# Line.net
KiCad netlist of a schematic drawn in EAGLE
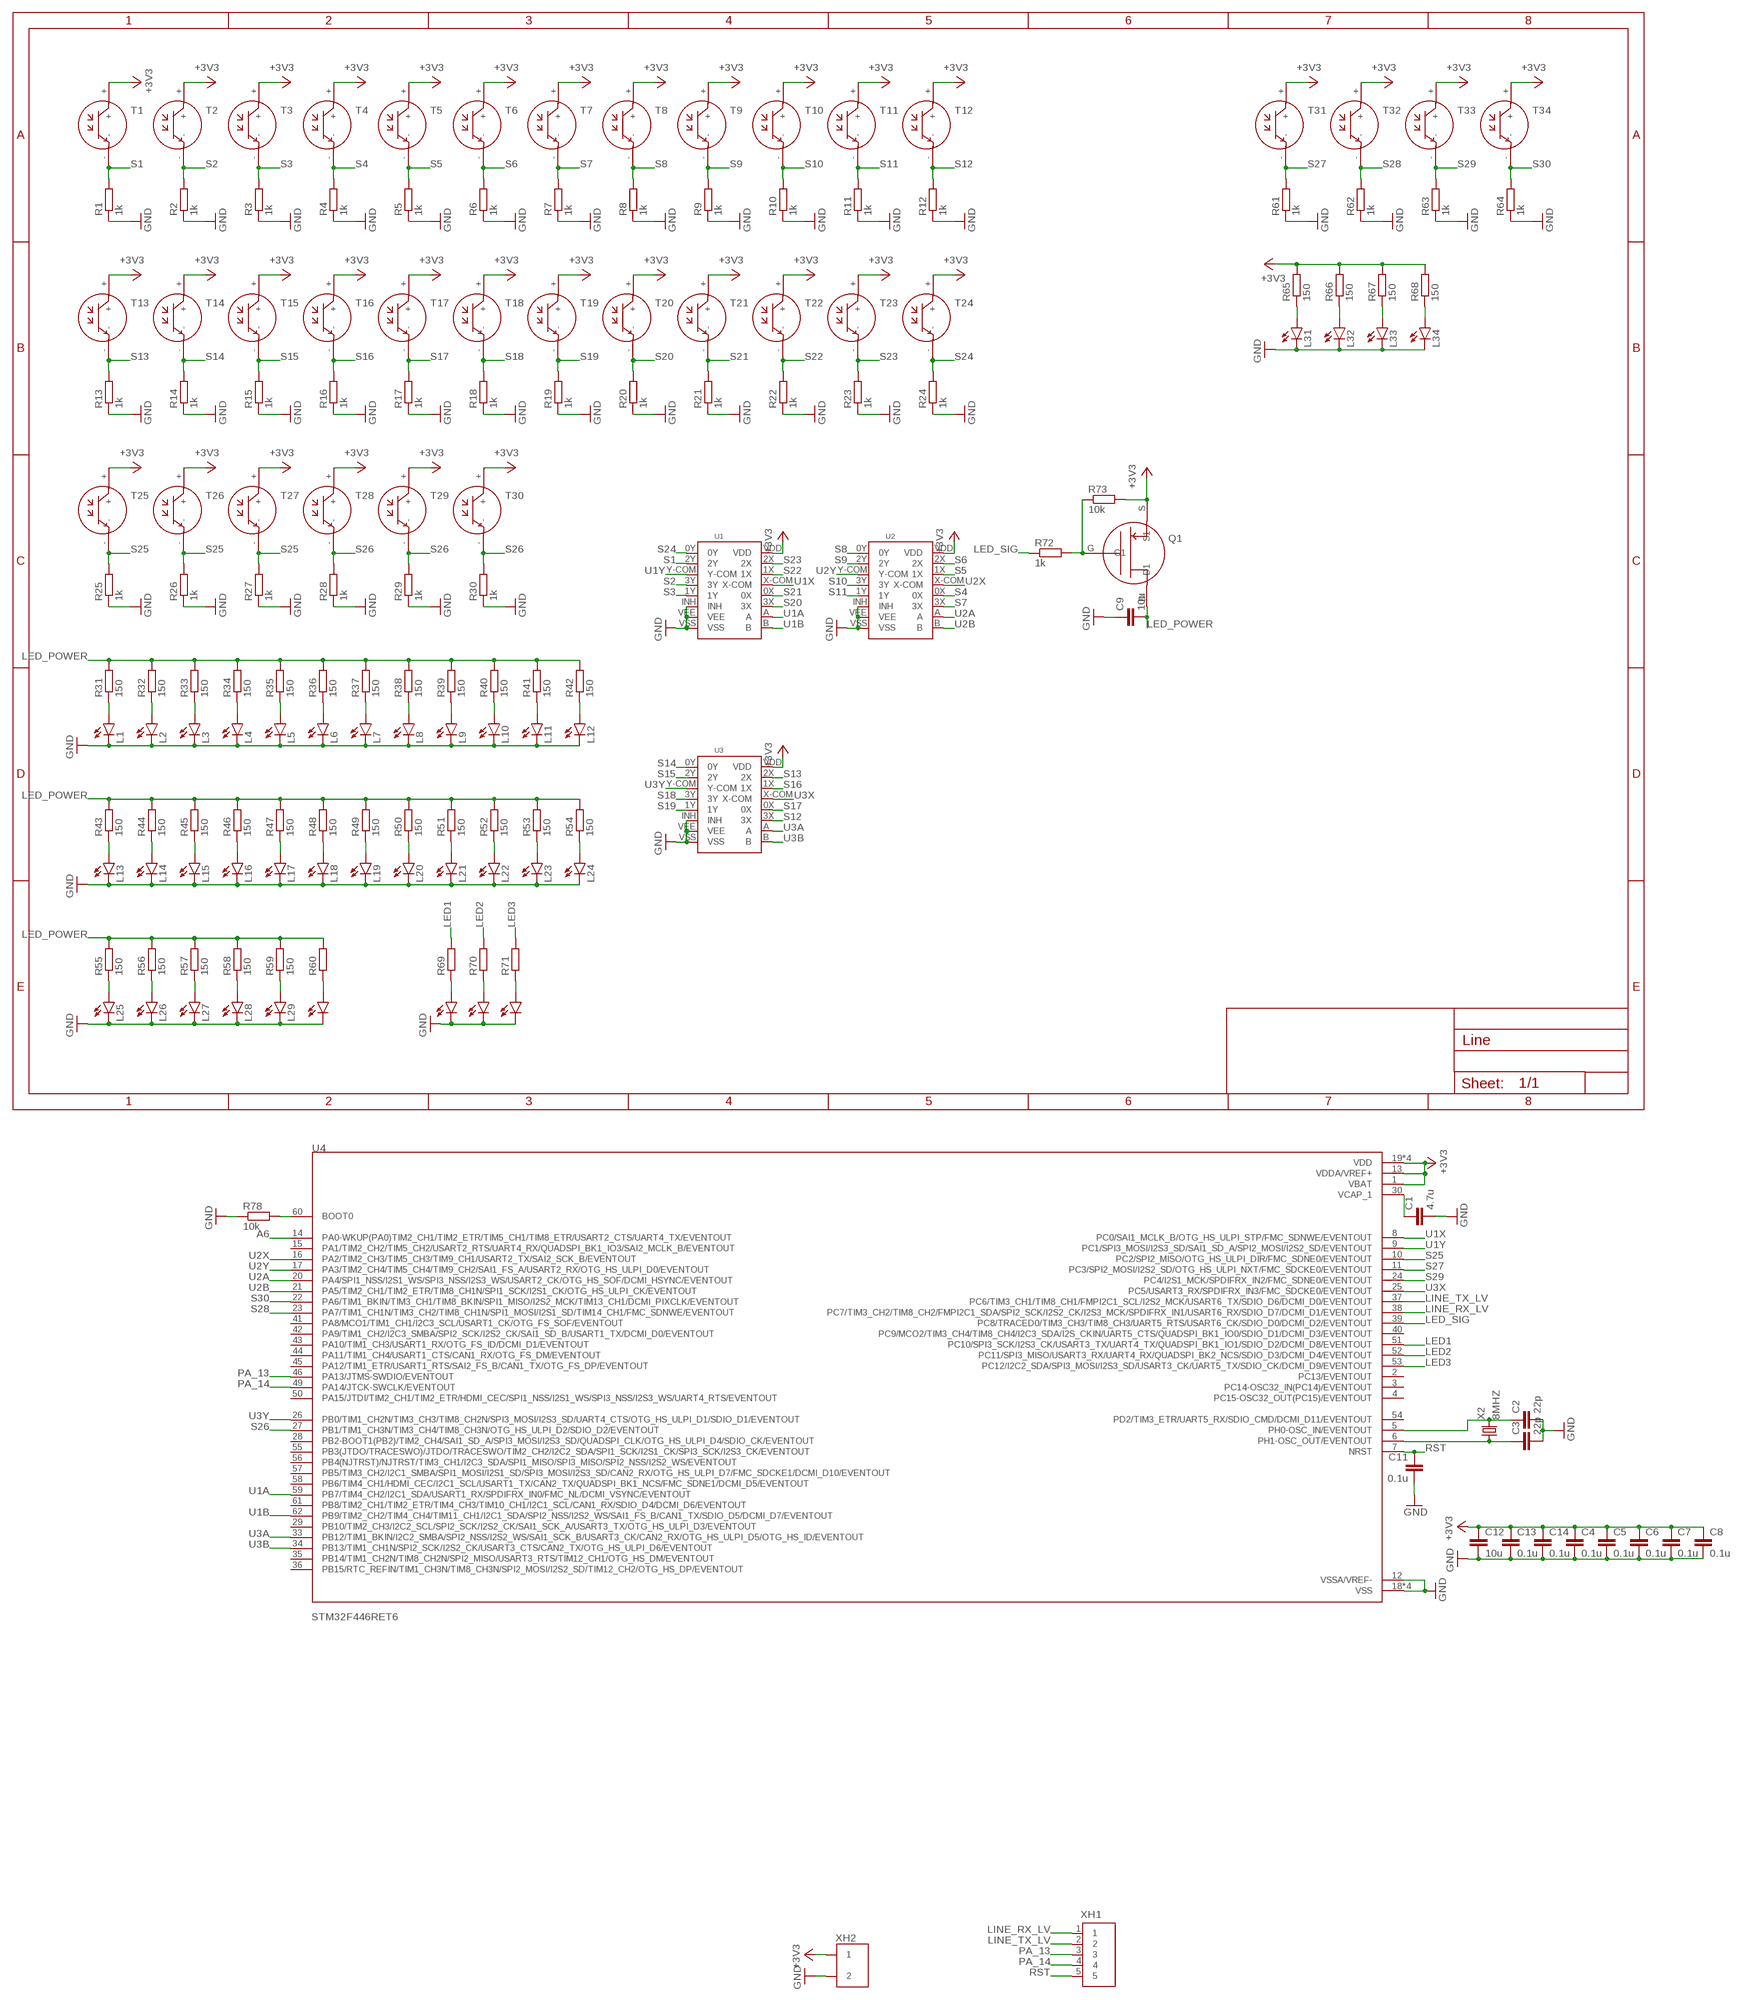
[diagram p0: schematic, sheet 1]

(export (version "E")
  (design (tool "Eeschema 10.0.6"))
  (components
    (comp (ref "C1")
      (value "4.7u")
      (footprint "eagle-import:C0603")
      (libsource (lib "eagle-import") (part "C-EUC0603"))
    )
    (comp (ref "C2")
      (value "22p")
      (footprint "eagle-import:C0603")
      (libsource (lib "eagle-import") (part "C-EUC0603"))
    )
    (comp (ref "C3")
      (value "22p")
      (footprint "eagle-import:C0603")
      (libsource (lib "eagle-import") (part "C-EUC0603"))
    )
    (comp (ref "C4")
      (value "0.1u")
      (footprint "eagle-import:C0603")
      (libsource (lib "eagle-import") (part "C-EUC0603"))
    )
    (comp (ref "C5")
      (value "0.1u")
      (footprint "eagle-import:C0603")
      (libsource (lib "eagle-import") (part "C-EUC0603"))
    )
    (comp (ref "C6")
      (value "0.1u")
      (footprint "eagle-import:C0603")
      (libsource (lib "eagle-import") (part "C-EUC0603"))
    )
    (comp (ref "C7")
      (value "0.1u")
      (footprint "eagle-import:C0603")
      (libsource (lib "eagle-import") (part "C-EUC0603"))
    )
    (comp (ref "C8")
      (value "0.1u")
      (footprint "eagle-import:C0603")
      (libsource (lib "eagle-import") (part "C-EUC0603"))
    )
    (comp (ref "C9")
      (value "10u")
      (footprint "eagle-import:C0805")
      (libsource (lib "eagle-import") (part "C-EUC0805"))
    )
    (comp (ref "C11")
      (value "0.1u")
      (footprint "eagle-import:C0603")
      (libsource (lib "eagle-import") (part "C-EUC0603"))
    )
    (comp (ref "C12")
      (value "10u")
      (footprint "eagle-import:C0805")
      (libsource (lib "eagle-import") (part "C-EUC0805"))
    )
    (comp (ref "C13")
      (value "0.1u")
      (footprint "eagle-import:C0603")
      (libsource (lib "eagle-import") (part "C-EUC0603"))
    )
    (comp (ref "C14")
      (value "0.1u")
      (footprint "eagle-import:C0603")
      (libsource (lib "eagle-import") (part "C-EUC0603"))
    )
    (comp (ref "L1")
      (value "SML-E12P8WT86")
      (footprint "eagle-import:LED_SML-LXFM0603SIC-TR")
      (libsource (lib "eagle-import") (part "SML-E12P8WT86"))
    )
    (comp (ref "L2")
      (value "SML-E12P8WT86")
      (footprint "eagle-import:LED_SML-LXFM0603SIC-TR")
      (libsource (lib "eagle-import") (part "SML-E12P8WT86"))
    )
    (comp (ref "L3")
      (value "SML-E12P8WT86")
      (footprint "eagle-import:LED_SML-LXFM0603SIC-TR")
      (libsource (lib "eagle-import") (part "SML-E12P8WT86"))
    )
    (comp (ref "L4")
      (value "SML-E12P8WT86")
      (footprint "eagle-import:LED_SML-LXFM0603SIC-TR")
      (libsource (lib "eagle-import") (part "SML-E12P8WT86"))
    )
    (comp (ref "L5")
      (value "SML-E12P8WT86")
      (footprint "eagle-import:LED_SML-LXFM0603SIC-TR")
      (libsource (lib "eagle-import") (part "SML-E12P8WT86"))
    )
    (comp (ref "L6")
      (value "SML-E12P8WT86")
      (footprint "eagle-import:LED_SML-LXFM0603SIC-TR")
      (libsource (lib "eagle-import") (part "SML-E12P8WT86"))
    )
    (comp (ref "L7")
      (value "SML-E12P8WT86")
      (footprint "eagle-import:LED_SML-LXFM0603SIC-TR")
      (libsource (lib "eagle-import") (part "SML-E12P8WT86"))
    )
    (comp (ref "L8")
      (value "SML-E12P8WT86")
      (footprint "eagle-import:LED_SML-LXFM0603SIC-TR")
      (libsource (lib "eagle-import") (part "SML-E12P8WT86"))
    )
    (comp (ref "L9")
      (value "SML-E12P8WT86")
      (footprint "eagle-import:LED_SML-LXFM0603SIC-TR")
      (libsource (lib "eagle-import") (part "SML-E12P8WT86"))
    )
    (comp (ref "L10")
      (value "SML-E12P8WT86")
      (footprint "eagle-import:LED_SML-LXFM0603SIC-TR")
      (libsource (lib "eagle-import") (part "SML-E12P8WT86"))
    )
    (comp (ref "L11")
      (value "SML-E12P8WT86")
      (footprint "eagle-import:LED_SML-LXFM0603SIC-TR")
      (libsource (lib "eagle-import") (part "SML-E12P8WT86"))
    )
    (comp (ref "L12")
      (value "SML-E12P8WT86")
      (footprint "eagle-import:LED_SML-LXFM0603SIC-TR")
      (libsource (lib "eagle-import") (part "SML-E12P8WT86"))
    )
    (comp (ref "L13")
      (value "SML-E12P8WT86")
      (footprint "eagle-import:LED_SML-LXFM0603SIC-TR")
      (libsource (lib "eagle-import") (part "SML-E12P8WT86"))
    )
    (comp (ref "L14")
      (value "SML-E12P8WT86")
      (footprint "eagle-import:LED_SML-LXFM0603SIC-TR")
      (libsource (lib "eagle-import") (part "SML-E12P8WT86"))
    )
    (comp (ref "L15")
      (value "SML-E12P8WT86")
      (footprint "eagle-import:LED_SML-LXFM0603SIC-TR")
      (libsource (lib "eagle-import") (part "SML-E12P8WT86"))
    )
    (comp (ref "L16")
      (value "SML-E12P8WT86")
      (footprint "eagle-import:LED_SML-LXFM0603SIC-TR")
      (libsource (lib "eagle-import") (part "SML-E12P8WT86"))
    )
    (comp (ref "L17")
      (value "SML-E12P8WT86")
      (footprint "eagle-import:LED_SML-LXFM0603SIC-TR")
      (libsource (lib "eagle-import") (part "SML-E12P8WT86"))
    )
    (comp (ref "L18")
      (value "SML-E12P8WT86")
      (footprint "eagle-import:LED_SML-LXFM0603SIC-TR")
      (libsource (lib "eagle-import") (part "SML-E12P8WT86"))
    )
    (comp (ref "L19")
      (value "SML-E12P8WT86")
      (footprint "eagle-import:LED_SML-LXFM0603SIC-TR")
      (libsource (lib "eagle-import") (part "SML-E12P8WT86"))
    )
    (comp (ref "L20")
      (value "SML-E12P8WT86")
      (footprint "eagle-import:LED_SML-LXFM0603SIC-TR")
      (libsource (lib "eagle-import") (part "SML-E12P8WT86"))
    )
    (comp (ref "L21")
      (value "SML-E12P8WT86")
      (footprint "eagle-import:LED_SML-LXFM0603SIC-TR")
      (libsource (lib "eagle-import") (part "SML-E12P8WT86"))
    )
    (comp (ref "L22")
      (value "SML-E12P8WT86")
      (footprint "eagle-import:LED_SML-LXFM0603SIC-TR")
      (libsource (lib "eagle-import") (part "SML-E12P8WT86"))
    )
    (comp (ref "L23")
      (value "SML-E12P8WT86")
      (footprint "eagle-import:LED_SML-LXFM0603SIC-TR")
      (libsource (lib "eagle-import") (part "SML-E12P8WT86"))
    )
    (comp (ref "L24")
      (value "SML-E12P8WT86")
      (footprint "eagle-import:LED_SML-LXFM0603SIC-TR")
      (libsource (lib "eagle-import") (part "SML-E12P8WT86"))
    )
    (comp (ref "L25")
      (value "SML-E12P8WT86")
      (footprint "eagle-import:LED_SML-LXFM0603SIC-TR")
      (libsource (lib "eagle-import") (part "SML-E12P8WT86"))
    )
    (comp (ref "L26")
      (value "SML-E12P8WT86")
      (footprint "eagle-import:LED_SML-LXFM0603SIC-TR")
      (libsource (lib "eagle-import") (part "SML-E12P8WT86"))
    )
    (comp (ref "L27")
      (value "SML-E12P8WT86")
      (footprint "eagle-import:LED_SML-LXFM0603SIC-TR")
      (libsource (lib "eagle-import") (part "SML-E12P8WT86"))
    )
    (comp (ref "L28")
      (value "SML-E12P8WT86")
      (footprint "eagle-import:LED_SML-LXFM0603SIC-TR")
      (libsource (lib "eagle-import") (part "SML-E12P8WT86"))
    )
    (comp (ref "L29")
      (value "SML-E12P8WT86")
      (footprint "eagle-import:LED_SML-LXFM0603SIC-TR")
      (libsource (lib "eagle-import") (part "SML-E12P8WT86"))
    )
    (comp (ref "L30")
      (value "SML-E12P8WT86")
      (footprint "eagle-import:LED_SML-LXFM0603SIC-TR")
      (libsource (lib "eagle-import") (part "SML-E12P8WT86"))
    )
    (comp (ref "L31")
      (value "SML-E12P8WT86")
      (footprint "eagle-import:LED_SML-LXFM0603SIC-TR")
      (libsource (lib "eagle-import") (part "SML-E12P8WT86"))
    )
    (comp (ref "L32")
      (value "SML-E12P8WT86")
      (footprint "eagle-import:LED_SML-LXFM0603SIC-TR")
      (libsource (lib "eagle-import") (part "SML-E12P8WT86"))
    )
    (comp (ref "L33")
      (value "SML-E12P8WT86")
      (footprint "eagle-import:LED_SML-LXFM0603SIC-TR")
      (libsource (lib "eagle-import") (part "SML-E12P8WT86"))
    )
    (comp (ref "L34")
      (value "SML-E12P8WT86")
      (footprint "eagle-import:LED_SML-LXFM0603SIC-TR")
      (libsource (lib "eagle-import") (part "SML-E12P8WT86"))
    )
    (comp (ref "L35")
      (value "SML-E12P8WT86")
      (footprint "eagle-import:LED_SML-LXFM0603SIC-TR")
      (libsource (lib "eagle-import") (part "SML-E12P8WT86"))
    )
    (comp (ref "L36")
      (value "SML-E12P8WT86")
      (footprint "eagle-import:LED_SML-LXFM0603SIC-TR")
      (libsource (lib "eagle-import") (part "SML-E12P8WT86"))
    )
    (comp (ref "L37")
      (value "SML-E12P8WT86")
      (footprint "eagle-import:LED_SML-LXFM0603SIC-TR")
      (libsource (lib "eagle-import") (part "SML-E12P8WT86"))
    )
    (comp (ref "Q1")
      (value "TJ60S04M3L")
      (footprint "eagle-import:DPACK")
      (libsource (lib "eagle-import") (part "TJ60S04M3L"))
    )
    (comp (ref "R1")
      (value "1k")
      (footprint "eagle-import:R0603")
      (libsource (lib "eagle-import") (part "R-EU_R0603"))
    )
    (comp (ref "R2")
      (value "1k")
      (footprint "eagle-import:R0603")
      (libsource (lib "eagle-import") (part "R-EU_R0603"))
    )
    (comp (ref "R3")
      (value "1k")
      (footprint "eagle-import:R0603")
      (libsource (lib "eagle-import") (part "R-EU_R0603"))
    )
    (comp (ref "R4")
      (value "1k")
      (footprint "eagle-import:R0603")
      (libsource (lib "eagle-import") (part "R-EU_R0603"))
    )
    (comp (ref "R5")
      (value "1k")
      (footprint "eagle-import:R0603")
      (libsource (lib "eagle-import") (part "R-EU_R0603"))
    )
    (comp (ref "R6")
      (value "1k")
      (footprint "eagle-import:R0603")
      (libsource (lib "eagle-import") (part "R-EU_R0603"))
    )
    (comp (ref "R7")
      (value "1k")
      (footprint "eagle-import:R0603")
      (libsource (lib "eagle-import") (part "R-EU_R0603"))
    )
    (comp (ref "R8")
      (value "1k")
      (footprint "eagle-import:R0603")
      (libsource (lib "eagle-import") (part "R-EU_R0603"))
    )
    (comp (ref "R9")
      (value "1k")
      (footprint "eagle-import:R0603")
      (libsource (lib "eagle-import") (part "R-EU_R0603"))
    )
    (comp (ref "R10")
      (value "1k")
      (footprint "eagle-import:R0603")
      (libsource (lib "eagle-import") (part "R-EU_R0603"))
    )
    (comp (ref "R11")
      (value "1k")
      (footprint "eagle-import:R0603")
      (libsource (lib "eagle-import") (part "R-EU_R0603"))
    )
    (comp (ref "R12")
      (value "1k")
      (footprint "eagle-import:R0603")
      (libsource (lib "eagle-import") (part "R-EU_R0603"))
    )
    (comp (ref "R13")
      (value "1k")
      (footprint "eagle-import:R0603")
      (libsource (lib "eagle-import") (part "R-EU_R0603"))
    )
    (comp (ref "R14")
      (value "1k")
      (footprint "eagle-import:R0603")
      (libsource (lib "eagle-import") (part "R-EU_R0603"))
    )
    (comp (ref "R15")
      (value "1k")
      (footprint "eagle-import:R0603")
      (libsource (lib "eagle-import") (part "R-EU_R0603"))
    )
    (comp (ref "R16")
      (value "1k")
      (footprint "eagle-import:R0603")
      (libsource (lib "eagle-import") (part "R-EU_R0603"))
    )
    (comp (ref "R17")
      (value "1k")
      (footprint "eagle-import:R0603")
      (libsource (lib "eagle-import") (part "R-EU_R0603"))
    )
    (comp (ref "R18")
      (value "1k")
      (footprint "eagle-import:R0603")
      (libsource (lib "eagle-import") (part "R-EU_R0603"))
    )
    (comp (ref "R19")
      (value "1k")
      (footprint "eagle-import:R0603")
      (libsource (lib "eagle-import") (part "R-EU_R0603"))
    )
    (comp (ref "R20")
      (value "1k")
      (footprint "eagle-import:R0603")
      (libsource (lib "eagle-import") (part "R-EU_R0603"))
    )
    (comp (ref "R21")
      (value "1k")
      (footprint "eagle-import:R0603")
      (libsource (lib "eagle-import") (part "R-EU_R0603"))
    )
    (comp (ref "R22")
      (value "1k")
      (footprint "eagle-import:R0603")
      (libsource (lib "eagle-import") (part "R-EU_R0603"))
    )
    (comp (ref "R23")
      (value "1k")
      (footprint "eagle-import:R0603")
      (libsource (lib "eagle-import") (part "R-EU_R0603"))
    )
    (comp (ref "R24")
      (value "1k")
      (footprint "eagle-import:R0603")
      (libsource (lib "eagle-import") (part "R-EU_R0603"))
    )
    (comp (ref "R25")
      (value "1k")
      (footprint "eagle-import:R0603")
      (libsource (lib "eagle-import") (part "R-EU_R0603"))
    )
    (comp (ref "R26")
      (value "1k")
      (footprint "eagle-import:R0603")
      (libsource (lib "eagle-import") (part "R-EU_R0603"))
    )
    (comp (ref "R27")
      (value "1k")
      (footprint "eagle-import:R0603")
      (libsource (lib "eagle-import") (part "R-EU_R0603"))
    )
    (comp (ref "R28")
      (value "1k")
      (footprint "eagle-import:R0603")
      (libsource (lib "eagle-import") (part "R-EU_R0603"))
    )
    (comp (ref "R29")
      (value "1k")
      (footprint "eagle-import:R0603")
      (libsource (lib "eagle-import") (part "R-EU_R0603"))
    )
    (comp (ref "R30")
      (value "1k")
      (footprint "eagle-import:R0603")
      (libsource (lib "eagle-import") (part "R-EU_R0603"))
    )
    (comp (ref "R31")
      (value "150")
      (footprint "eagle-import:R0603")
      (libsource (lib "eagle-import") (part "R-EU_R0603"))
    )
    (comp (ref "R32")
      (value "150")
      (footprint "eagle-import:R0603")
      (libsource (lib "eagle-import") (part "R-EU_R0603"))
    )
    (comp (ref "R33")
      (value "150")
      (footprint "eagle-import:R0603")
      (libsource (lib "eagle-import") (part "R-EU_R0603"))
    )
    (comp (ref "R34")
      (value "150")
      (footprint "eagle-import:R0603")
      (libsource (lib "eagle-import") (part "R-EU_R0603"))
    )
    (comp (ref "R35")
      (value "150")
      (footprint "eagle-import:R0603")
      (libsource (lib "eagle-import") (part "R-EU_R0603"))
    )
    (comp (ref "R36")
      (value "150")
      (footprint "eagle-import:R0603")
      (libsource (lib "eagle-import") (part "R-EU_R0603"))
    )
    (comp (ref "R37")
      (value "150")
      (footprint "eagle-import:R0603")
      (libsource (lib "eagle-import") (part "R-EU_R0603"))
    )
    (comp (ref "R38")
      (value "150")
      (footprint "eagle-import:R0603")
      (libsource (lib "eagle-import") (part "R-EU_R0603"))
    )
    (comp (ref "R39")
      (value "150")
      (footprint "eagle-import:R0603")
      (libsource (lib "eagle-import") (part "R-EU_R0603"))
    )
    (comp (ref "R40")
      (value "150")
      (footprint "eagle-import:R0603")
      (libsource (lib "eagle-import") (part "R-EU_R0603"))
    )
    (comp (ref "R41")
      (value "150")
      (footprint "eagle-import:R0603")
      (libsource (lib "eagle-import") (part "R-EU_R0603"))
    )
    (comp (ref "R42")
      (value "150")
      (footprint "eagle-import:R0603")
      (libsource (lib "eagle-import") (part "R-EU_R0603"))
    )
    (comp (ref "R43")
      (value "150")
      (footprint "eagle-import:R0603")
      (libsource (lib "eagle-import") (part "R-EU_R0603"))
    )
    (comp (ref "R44")
      (value "150")
      (footprint "eagle-import:R0603")
      (libsource (lib "eagle-import") (part "R-EU_R0603"))
    )
    (comp (ref "R45")
      (value "150")
      (footprint "eagle-import:R0603")
      (libsource (lib "eagle-import") (part "R-EU_R0603"))
    )
    (comp (ref "R46")
      (value "150")
      (footprint "eagle-import:R0603")
      (libsource (lib "eagle-import") (part "R-EU_R0603"))
    )
    (comp (ref "R47")
      (value "150")
      (footprint "eagle-import:R0603")
      (libsource (lib "eagle-import") (part "R-EU_R0603"))
    )
    (comp (ref "R48")
      (value "150")
      (footprint "eagle-import:R0603")
      (libsource (lib "eagle-import") (part "R-EU_R0603"))
    )
    (comp (ref "R49")
      (value "150")
      (footprint "eagle-import:R0603")
      (libsource (lib "eagle-import") (part "R-EU_R0603"))
    )
    (comp (ref "R50")
      (value "150")
      (footprint "eagle-import:R0603")
      (libsource (lib "eagle-import") (part "R-EU_R0603"))
    )
    (comp (ref "R51")
      (value "150")
      (footprint "eagle-import:R0603")
      (libsource (lib "eagle-import") (part "R-EU_R0603"))
    )
    (comp (ref "R52")
      (value "150")
      (footprint "eagle-import:R0603")
      (libsource (lib "eagle-import") (part "R-EU_R0603"))
    )
    (comp (ref "R53")
      (value "150")
      (footprint "eagle-import:R0603")
      (libsource (lib "eagle-import") (part "R-EU_R0603"))
    )
    (comp (ref "R54")
      (value "150")
      (footprint "eagle-import:R0603")
      (libsource (lib "eagle-import") (part "R-EU_R0603"))
    )
    (comp (ref "R55")
      (value "150")
      (footprint "eagle-import:R0603")
      (libsource (lib "eagle-import") (part "R-EU_R0603"))
    )
    (comp (ref "R56")
      (value "150")
      (footprint "eagle-import:R0603")
      (libsource (lib "eagle-import") (part "R-EU_R0603"))
    )
    (comp (ref "R57")
      (value "150")
      (footprint "eagle-import:R0603")
      (libsource (lib "eagle-import") (part "R-EU_R0603"))
    )
    (comp (ref "R58")
      (value "150")
      (footprint "eagle-import:R0603")
      (libsource (lib "eagle-import") (part "R-EU_R0603"))
    )
    (comp (ref "R59")
      (value "150")
      (footprint "eagle-import:R0603")
      (libsource (lib "eagle-import") (part "R-EU_R0603"))
    )
    (comp (ref "R60")
      (value "150")
      (footprint "eagle-import:R0603")
      (libsource (lib "eagle-import") (part "R-EU_R0603"))
    )
    (comp (ref "R61")
      (value "1k")
      (footprint "eagle-import:R0603")
      (libsource (lib "eagle-import") (part "R-EU_R0603"))
    )
    (comp (ref "R62")
      (value "1k")
      (footprint "eagle-import:R0603")
      (libsource (lib "eagle-import") (part "R-EU_R0603"))
    )
    (comp (ref "R63")
      (value "1k")
      (footprint "eagle-import:R0603")
      (libsource (lib "eagle-import") (part "R-EU_R0603"))
    )
    (comp (ref "R64")
      (value "1k")
      (footprint "eagle-import:R0603")
      (libsource (lib "eagle-import") (part "R-EU_R0603"))
    )
    (comp (ref "R65")
      (value "150")
      (footprint "eagle-import:R0603")
      (libsource (lib "eagle-import") (part "R-EU_R0603"))
    )
    (comp (ref "R66")
      (value "150")
      (footprint "eagle-import:R0603")
      (libsource (lib "eagle-import") (part "R-EU_R0603"))
    )
    (comp (ref "R67")
      (value "150")
      (footprint "eagle-import:R0603")
      (libsource (lib "eagle-import") (part "R-EU_R0603"))
    )
    (comp (ref "R68")
      (value "150")
      (footprint "eagle-import:R0603")
      (libsource (lib "eagle-import") (part "R-EU_R0603"))
    )
    (comp (ref "R69")
      (value "150")
      (footprint "eagle-import:R0603")
      (libsource (lib "eagle-import") (part "R-EU_R0603"))
    )
    (comp (ref "R70")
      (value "150")
      (footprint "eagle-import:R0603")
      (libsource (lib "eagle-import") (part "R-EU_R0603"))
    )
    (comp (ref "R71")
      (value "150")
      (footprint "eagle-import:R0603")
      (libsource (lib "eagle-import") (part "R-EU_R0603"))
    )
    (comp (ref "R72")
      (value "1k")
      (footprint "eagle-import:R0603")
      (libsource (lib "eagle-import") (part "R-EU_R0603"))
    )
    (comp (ref "R73")
      (value "10k")
      (footprint "eagle-import:R0603")
      (libsource (lib "eagle-import") (part "R-EU_R0603"))
    )
    (comp (ref "R78")
      (value "10k")
      (footprint "eagle-import:R0603")
      (libsource (lib "eagle-import") (part "R-EU_R0603"))
    )
    (comp (ref "T1")
      (value "NJL7302L-F3")
      (footprint "eagle-import:NJL7302L-F3")
      (libsource (lib "eagle-import") (part "NJL7302L-F3"))
    )
    (comp (ref "T2")
      (value "NJL7302L-F3")
      (footprint "eagle-import:NJL7302L-F3")
      (libsource (lib "eagle-import") (part "NJL7302L-F3"))
    )
    (comp (ref "T3")
      (value "NJL7302L-F3")
      (footprint "eagle-import:NJL7302L-F3")
      (libsource (lib "eagle-import") (part "NJL7302L-F3"))
    )
    (comp (ref "T4")
      (value "NJL7302L-F3")
      (footprint "eagle-import:NJL7302L-F3")
      (libsource (lib "eagle-import") (part "NJL7302L-F3"))
    )
    (comp (ref "T5")
      (value "NJL7302L-F3")
      (footprint "eagle-import:NJL7302L-F3")
      (libsource (lib "eagle-import") (part "NJL7302L-F3"))
    )
    (comp (ref "T6")
      (value "NJL7302L-F3")
      (footprint "eagle-import:NJL7302L-F3")
      (libsource (lib "eagle-import") (part "NJL7302L-F3"))
    )
    (comp (ref "T7")
      (value "NJL7302L-F3")
      (footprint "eagle-import:NJL7302L-F3")
      (libsource (lib "eagle-import") (part "NJL7302L-F3"))
    )
    (comp (ref "T8")
      (value "NJL7302L-F3")
      (footprint "eagle-import:NJL7302L-F3")
      (libsource (lib "eagle-import") (part "NJL7302L-F3"))
    )
    (comp (ref "T9")
      (value "NJL7302L-F3")
      (footprint "eagle-import:NJL7302L-F3")
      (libsource (lib "eagle-import") (part "NJL7302L-F3"))
    )
    (comp (ref "T10")
      (value "NJL7302L-F3")
      (footprint "eagle-import:NJL7302L-F3")
      (libsource (lib "eagle-import") (part "NJL7302L-F3"))
    )
    (comp (ref "T11")
      (value "NJL7302L-F3")
      (footprint "eagle-import:NJL7302L-F3")
      (libsource (lib "eagle-import") (part "NJL7302L-F3"))
    )
    (comp (ref "T12")
      (value "NJL7302L-F3")
      (footprint "eagle-import:NJL7302L-F3")
      (libsource (lib "eagle-import") (part "NJL7302L-F3"))
    )
    (comp (ref "T13")
      (value "NJL7302L-F3")
      (footprint "eagle-import:NJL7302L-F3")
      (libsource (lib "eagle-import") (part "NJL7302L-F3"))
    )
    (comp (ref "T14")
      (value "NJL7302L-F3")
      (footprint "eagle-import:NJL7302L-F3")
      (libsource (lib "eagle-import") (part "NJL7302L-F3"))
    )
    (comp (ref "T15")
      (value "NJL7302L-F3")
      (footprint "eagle-import:NJL7302L-F3")
      (libsource (lib "eagle-import") (part "NJL7302L-F3"))
    )
    (comp (ref "T16")
      (value "NJL7302L-F3")
      (footprint "eagle-import:NJL7302L-F3")
      (libsource (lib "eagle-import") (part "NJL7302L-F3"))
    )
    (comp (ref "T17")
      (value "NJL7302L-F3")
      (footprint "eagle-import:NJL7302L-F3")
      (libsource (lib "eagle-import") (part "NJL7302L-F3"))
    )
    (comp (ref "T18")
      (value "NJL7302L-F3")
      (footprint "eagle-import:NJL7302L-F3")
      (libsource (lib "eagle-import") (part "NJL7302L-F3"))
    )
    (comp (ref "T19")
      (value "NJL7302L-F3")
      (footprint "eagle-import:NJL7302L-F3")
      (libsource (lib "eagle-import") (part "NJL7302L-F3"))
    )
    (comp (ref "T20")
      (value "NJL7302L-F3")
      (footprint "eagle-import:NJL7302L-F3")
      (libsource (lib "eagle-import") (part "NJL7302L-F3"))
    )
    (comp (ref "T21")
      (value "NJL7302L-F3")
      (footprint "eagle-import:NJL7302L-F3")
      (libsource (lib "eagle-import") (part "NJL7302L-F3"))
    )
    (comp (ref "T22")
      (value "NJL7302L-F3")
      (footprint "eagle-import:NJL7302L-F3")
      (libsource (lib "eagle-import") (part "NJL7302L-F3"))
    )
    (comp (ref "T23")
      (value "NJL7302L-F3")
      (footprint "eagle-import:NJL7302L-F3")
      (libsource (lib "eagle-import") (part "NJL7302L-F3"))
    )
    (comp (ref "T24")
      (value "NJL7302L-F3")
      (footprint "eagle-import:NJL7302L-F3")
      (libsource (lib "eagle-import") (part "NJL7302L-F3"))
    )
    (comp (ref "T25")
      (value "NJL7302L-F3")
      (footprint "eagle-import:NJL7302L-F3")
      (libsource (lib "eagle-import") (part "NJL7302L-F3"))
    )
    (comp (ref "T26")
      (value "NJL7302L-F3")
      (footprint "eagle-import:NJL7302L-F3")
      (libsource (lib "eagle-import") (part "NJL7302L-F3"))
    )
    (comp (ref "T27")
      (value "NJL7302L-F3")
      (footprint "eagle-import:NJL7302L-F3")
      (libsource (lib "eagle-import") (part "NJL7302L-F3"))
    )
    (comp (ref "T28")
      (value "NJL7302L-F3")
      (footprint "eagle-import:NJL7302L-F3")
      (libsource (lib "eagle-import") (part "NJL7302L-F3"))
    )
    (comp (ref "T29")
      (value "NJL7302L-F3")
      (footprint "eagle-import:NJL7302L-F3")
      (libsource (lib "eagle-import") (part "NJL7302L-F3"))
    )
    (comp (ref "T30")
      (value "NJL7302L-F3")
      (footprint "eagle-import:NJL7302L-F3")
      (libsource (lib "eagle-import") (part "NJL7302L-F3"))
    )
    (comp (ref "T31")
      (value "NJL7302L-F3")
      (footprint "eagle-import:NJL7302L-F3")
      (libsource (lib "eagle-import") (part "NJL7302L-F3"))
    )
    (comp (ref "T32")
      (value "NJL7302L-F3")
      (footprint "eagle-import:NJL7302L-F3")
      (libsource (lib "eagle-import") (part "NJL7302L-F3"))
    )
    (comp (ref "T33")
      (value "NJL7302L-F3")
      (footprint "eagle-import:NJL7302L-F3")
      (libsource (lib "eagle-import") (part "NJL7302L-F3"))
    )
    (comp (ref "T34")
      (value "NJL7302L-F3")
      (footprint "eagle-import:NJL7302L-F3")
      (libsource (lib "eagle-import") (part "NJL7302L-F3"))
    )
    (comp (ref "U1")
      (value "TC4051BP")
      (footprint "eagle-import:TC4051BP")
      (libsource (lib "eagle-import") (part "TC4051BP"))
    )
    (comp (ref "U2")
      (value "TC4051BP")
      (footprint "eagle-import:TC4051BP")
      (libsource (lib "eagle-import") (part "TC4051BP"))
    )
    (comp (ref "U3")
      (value "TC4051BP")
      (footprint "eagle-import:TC4051BP")
      (libsource (lib "eagle-import") (part "TC4051BP"))
    )
    (comp (ref "U4")
      (value "STM32F446RET6")
      (footprint "eagle-import:QFP50P1200X1200X160-64N")
      (fields (field (name "MF") "STMicroelectronics"))
      (libsource (lib "eagle-import") (part "STM32F446RET6"))
    )
    (comp (ref "X2")
      (value "8MHZ")
      (footprint "eagle-import:16MHZ")
      (libsource (lib "eagle-import") (part "16MHZ"))
    )
    (comp (ref "XH1") (value "5B") (footprint "eagle-import:5B") (libsource (lib "eagle-import") (part "5B")))
    (comp (ref "XH2") (value "2B") (footprint "eagle-import:2B") (libsource (lib "eagle-import") (part "2B")))
  )
  (nets
    (net (code "1") (name "+3V3") (class "Default")
      (node (ref "C12") (pin "1") (pinfunction "1_1") (pintype "passive"))
      (node (ref "C13") (pin "1") (pinfunction "1_1") (pintype "passive"))
      (node (ref "C14") (pin "1") (pinfunction "1_1") (pintype "passive"))
      (node (ref "C4") (pin "1") (pinfunction "1_1") (pintype "passive"))
      (node (ref "C5") (pin "1") (pinfunction "1_1") (pintype "passive"))
      (node (ref "C6") (pin "1") (pinfunction "1_1") (pintype "passive"))
      (node (ref "C7") (pin "1") (pinfunction "1_1") (pintype "passive"))
      (node (ref "C8") (pin "1") (pinfunction "1_1") (pintype "passive"))
      (node (ref "Q1") (pin "S") (pinfunction "S1_S") (pintype "bidirectional"))
      (node (ref "R65") (pin "2") (pinfunction "2_2") (pintype "passive"))
      (node (ref "R66") (pin "2") (pinfunction "2_2") (pintype "passive"))
      (node (ref "R67") (pin "2") (pinfunction "2_2") (pintype "passive"))
      (node (ref "R68") (pin "2") (pinfunction "2_2") (pintype "passive"))
      (node (ref "R73") (pin "2") (pinfunction "2_2") (pintype "passive"))
      (node (ref "T1") (pin "+") (pinfunction "+_+") (pintype "bidirectional"))
      (node (ref "T10") (pin "+") (pinfunction "+_+") (pintype "bidirectional"))
      (node (ref "T11") (pin "+") (pinfunction "+_+") (pintype "bidirectional"))
      (node (ref "T12") (pin "+") (pinfunction "+_+") (pintype "bidirectional"))
      (node (ref "T13") (pin "+") (pinfunction "+_+") (pintype "bidirectional"))
      (node (ref "T14") (pin "+") (pinfunction "+_+") (pintype "bidirectional"))
      (node (ref "T15") (pin "+") (pinfunction "+_+") (pintype "bidirectional"))
      (node (ref "T16") (pin "+") (pinfunction "+_+") (pintype "bidirectional"))
      (node (ref "T17") (pin "+") (pinfunction "+_+") (pintype "bidirectional"))
      (node (ref "T18") (pin "+") (pinfunction "+_+") (pintype "bidirectional"))
      (node (ref "T19") (pin "+") (pinfunction "+_+") (pintype "bidirectional"))
      (node (ref "T2") (pin "+") (pinfunction "+_+") (pintype "bidirectional"))
      (node (ref "T20") (pin "+") (pinfunction "+_+") (pintype "bidirectional"))
      (node (ref "T21") (pin "+") (pinfunction "+_+") (pintype "bidirectional"))
      (node (ref "T22") (pin "+") (pinfunction "+_+") (pintype "bidirectional"))
      (node (ref "T23") (pin "+") (pinfunction "+_+") (pintype "bidirectional"))
      (node (ref "T24") (pin "+") (pinfunction "+_+") (pintype "bidirectional"))
      (node (ref "T25") (pin "+") (pinfunction "+_+") (pintype "bidirectional"))
      (node (ref "T26") (pin "+") (pinfunction "+_+") (pintype "bidirectional"))
      (node (ref "T27") (pin "+") (pinfunction "+_+") (pintype "bidirectional"))
      (node (ref "T28") (pin "+") (pinfunction "+_+") (pintype "bidirectional"))
      (node (ref "T29") (pin "+") (pinfunction "+_+") (pintype "bidirectional"))
      (node (ref "T3") (pin "+") (pinfunction "+_+") (pintype "bidirectional"))
      (node (ref "T30") (pin "+") (pinfunction "+_+") (pintype "bidirectional"))
      (node (ref "T31") (pin "+") (pinfunction "+_+") (pintype "bidirectional"))
      (node (ref "T32") (pin "+") (pinfunction "+_+") (pintype "bidirectional"))
      (node (ref "T33") (pin "+") (pinfunction "+_+") (pintype "bidirectional"))
      (node (ref "T34") (pin "+") (pinfunction "+_+") (pintype "bidirectional"))
      (node (ref "T4") (pin "+") (pinfunction "+_+") (pintype "bidirectional"))
      (node (ref "T5") (pin "+") (pinfunction "+_+") (pintype "bidirectional"))
      (node (ref "T6") (pin "+") (pinfunction "+_+") (pintype "bidirectional"))
      (node (ref "T7") (pin "+") (pinfunction "+_+") (pintype "bidirectional"))
      (node (ref "T8") (pin "+") (pinfunction "+_+") (pintype "bidirectional"))
      (node (ref "T9") (pin "+") (pinfunction "+_+") (pintype "bidirectional"))
      (node (ref "U1") (pin "VDD") (pinfunction "VDD_VDD") (pintype "bidirectional"))
      (node (ref "U2") (pin "VDD") (pinfunction "VDD_VDD") (pintype "bidirectional"))
      (node (ref "U3") (pin "VDD") (pinfunction "VDD_VDD") (pintype "bidirectional"))
      (node (ref "U4") (pin "1") (pinfunction "VBAT_1") (pintype "power_in"))
      (node (ref "U4") (pin "13") (pinfunction "VDDA/VREF+_13") (pintype "power_in"))
      (node (ref "U4") (pin "19") (pinfunction "VDD_19") (pintype "power_in"))
      (node (ref "U4") (pin "32") (pinfunction "VDD_32") (pintype "power_in"))
      (node (ref "U4") (pin "48") (pinfunction "VDD_48") (pintype "power_in"))
      (node (ref "U4") (pin "64") (pinfunction "VDD_64") (pintype "power_in"))
      (node (ref "XH2") (pin "P$1") (pinfunction "1_P$1") (pintype "bidirectional"))
    )
    (net (code "2") (name "/A6") (class "Default")
      (node (ref "U4") (pin "14") (pinfunction "PA0-WKUP(PA0)TIM2_CH1/TIM2_ETR/TIM5_CH1/TIM8_ETR/USART2_CTS/UART4_TX/EVENTOUT_14") (pintype "bidirectional"))
    )
    (net (code "3") (name "/LED1") (class "Default")
      (node (ref "R69") (pin "2") (pinfunction "2_2") (pintype "passive"))
      (node (ref "U4") (pin "51") (pinfunction "PC10/SPI3_SCK/I2S3_CK/USART3_TX/UART4_TX/QUADSPI_BK1_IO1/SDIO_D2/DCMI_D8/EVENTOUT_51") (pintype "bidirectional"))
    )
    (net (code "4") (name "/LED2") (class "Default")
      (node (ref "R70") (pin "2") (pinfunction "2_2") (pintype "passive"))
      (node (ref "U4") (pin "52") (pinfunction "PC11/SPI3_MISO/USART3_RX/UART4_RX/QUADSPI_BK2_NCS/SDIO_D3/DCMI_D4/EVENTOUT_52") (pintype "bidirectional"))
    )
    (net (code "5") (name "/LED3") (class "Default")
      (node (ref "R71") (pin "2") (pinfunction "2_2") (pintype "passive"))
      (node (ref "U4") (pin "53") (pinfunction "PC12/I2C2_SDA/SPI3_MOSI/I2S3_SD/USART3_CK/UART5_TX/SDIO_CK/DCMI_D9/EVENTOUT_53") (pintype "bidirectional"))
    )
    (net (code "6") (name "/LED_POWER") (class "Default")
      (node (ref "C9") (pin "2") (pinfunction "2_2") (pintype "passive"))
      (node (ref "Q1") (pin "D") (pinfunction "D1_D") (pintype "bidirectional"))
      (node (ref "R31") (pin "2") (pinfunction "2_2") (pintype "passive"))
      (node (ref "R32") (pin "2") (pinfunction "2_2") (pintype "passive"))
      (node (ref "R33") (pin "2") (pinfunction "2_2") (pintype "passive"))
      (node (ref "R34") (pin "2") (pinfunction "2_2") (pintype "passive"))
      (node (ref "R35") (pin "2") (pinfunction "2_2") (pintype "passive"))
      (node (ref "R36") (pin "2") (pinfunction "2_2") (pintype "passive"))
      (node (ref "R37") (pin "2") (pinfunction "2_2") (pintype "passive"))
      (node (ref "R38") (pin "2") (pinfunction "2_2") (pintype "passive"))
      (node (ref "R39") (pin "2") (pinfunction "2_2") (pintype "passive"))
      (node (ref "R40") (pin "2") (pinfunction "2_2") (pintype "passive"))
      (node (ref "R41") (pin "2") (pinfunction "2_2") (pintype "passive"))
      (node (ref "R42") (pin "2") (pinfunction "2_2") (pintype "passive"))
      (node (ref "R43") (pin "2") (pinfunction "2_2") (pintype "passive"))
      (node (ref "R44") (pin "2") (pinfunction "2_2") (pintype "passive"))
      (node (ref "R45") (pin "2") (pinfunction "2_2") (pintype "passive"))
      (node (ref "R46") (pin "2") (pinfunction "2_2") (pintype "passive"))
      (node (ref "R47") (pin "2") (pinfunction "2_2") (pintype "passive"))
      (node (ref "R48") (pin "2") (pinfunction "2_2") (pintype "passive"))
      (node (ref "R49") (pin "2") (pinfunction "2_2") (pintype "passive"))
      (node (ref "R50") (pin "2") (pinfunction "2_2") (pintype "passive"))
      (node (ref "R51") (pin "2") (pinfunction "2_2") (pintype "passive"))
      (node (ref "R52") (pin "2") (pinfunction "2_2") (pintype "passive"))
      (node (ref "R53") (pin "2") (pinfunction "2_2") (pintype "passive"))
      (node (ref "R54") (pin "2") (pinfunction "2_2") (pintype "passive"))
      (node (ref "R55") (pin "2") (pinfunction "2_2") (pintype "passive"))
      (node (ref "R56") (pin "2") (pinfunction "2_2") (pintype "passive"))
      (node (ref "R57") (pin "2") (pinfunction "2_2") (pintype "passive"))
      (node (ref "R58") (pin "2") (pinfunction "2_2") (pintype "passive"))
      (node (ref "R59") (pin "2") (pinfunction "2_2") (pintype "passive"))
      (node (ref "R60") (pin "2") (pinfunction "2_2") (pintype "passive"))
    )
    (net (code "7") (name "/LED_SIG") (class "Default")
      (node (ref "R72") (pin "1") (pinfunction "1_1") (pintype "passive"))
      (node (ref "U4") (pin "39") (pinfunction "PC8/TRACED0/TIM3_CH3/TIM8_CH3/UART5_RTS/USART6_CK/SDIO_D0/DCMI_D2/EVENTOUT_39") (pintype "bidirectional"))
    )
    (net (code "8") (name "/LINE_RX_LV") (class "Default")
      (node (ref "U4") (pin "38") (pinfunction "PC7/TIM3_CH2/TIM8_CH2/FMPI2C1_SDA/SPI2_SCK/I2S2_CK/I2S3_MCK/SPDIFRX_IN1/USART6_RX/SDIO_D7/DCMI_D1/EVENTOUT_38") (pintype "bidirectional"))
      (node (ref "XH1") (pin "1") (pinfunction "1_1") (pintype "bidirectional"))
    )
    (net (code "9") (name "/LINE_TX_LV") (class "Default")
      (node (ref "U4") (pin "37") (pinfunction "PC6/TIM3_CH1/TIM8_CH1/FMPI2C1_SCL/I2S2_MCK/USART6_TX/SDIO_D6/DCMI_D0/EVENTOUT_37") (pintype "bidirectional"))
      (node (ref "XH1") (pin "2") (pinfunction "2_2") (pintype "bidirectional"))
    )
    (net (code "10") (name "/PA_13") (class "Default")
      (node (ref "U4") (pin "46") (pinfunction "PA13/JTMS-SWDIO/EVENTOUT_46") (pintype "bidirectional"))
      (node (ref "XH1") (pin "3") (pinfunction "3_3") (pintype "bidirectional"))
    )
    (net (code "11") (name "/PA_14") (class "Default")
      (node (ref "U4") (pin "49") (pinfunction "PA14/JTCK-SWCLK/EVENTOUT_49") (pintype "bidirectional"))
      (node (ref "XH1") (pin "4") (pinfunction "4_4") (pintype "bidirectional"))
    )
    (net (code "12") (name "/RST") (class "Default")
      (node (ref "C11") (pin "1") (pinfunction "1_1") (pintype "passive"))
      (node (ref "U4") (pin "7") (pinfunction "NRST_7") (pintype "bidirectional"))
      (node (ref "XH1") (pin "5") (pinfunction "5_5") (pintype "bidirectional"))
    )
    (net (code "13") (name "/S1") (class "Default")
      (node (ref "R1") (pin "2") (pinfunction "2_2") (pintype "passive"))
      (node (ref "T1") (pin "-") (pinfunction "-_-") (pintype "bidirectional"))
      (node (ref "U1") (pin "2Y") (pinfunction "2Y_2Y") (pintype "bidirectional"))
    )
    (net (code "14") (name "/S2") (class "Default")
      (node (ref "R2") (pin "2") (pinfunction "2_2") (pintype "passive"))
      (node (ref "T2") (pin "-") (pinfunction "-_-") (pintype "bidirectional"))
      (node (ref "U1") (pin "3Y") (pinfunction "3Y_3Y") (pintype "bidirectional"))
    )
    (net (code "15") (name "/S3") (class "Default")
      (node (ref "R3") (pin "2") (pinfunction "2_2") (pintype "passive"))
      (node (ref "T3") (pin "-") (pinfunction "-_-") (pintype "bidirectional"))
      (node (ref "U1") (pin "1Y") (pinfunction "1Y_1Y") (pintype "bidirectional"))
    )
    (net (code "16") (name "/S4") (class "Default")
      (node (ref "R4") (pin "2") (pinfunction "2_2") (pintype "passive"))
      (node (ref "T4") (pin "-") (pinfunction "-_-") (pintype "bidirectional"))
      (node (ref "U2") (pin "0X") (pinfunction "0X_0X") (pintype "bidirectional"))
    )
    (net (code "17") (name "/S5") (class "Default")
      (node (ref "R5") (pin "2") (pinfunction "2_2") (pintype "passive"))
      (node (ref "T5") (pin "-") (pinfunction "-_-") (pintype "bidirectional"))
      (node (ref "U2") (pin "1X") (pinfunction "1X_1X") (pintype "bidirectional"))
    )
    (net (code "18") (name "/S6") (class "Default")
      (node (ref "R6") (pin "2") (pinfunction "2_2") (pintype "passive"))
      (node (ref "T6") (pin "-") (pinfunction "-_-") (pintype "bidirectional"))
      (node (ref "U2") (pin "2X") (pinfunction "2X_2X") (pintype "bidirectional"))
    )
    (net (code "19") (name "/S7") (class "Default")
      (node (ref "R7") (pin "2") (pinfunction "2_2") (pintype "passive"))
      (node (ref "T7") (pin "-") (pinfunction "-_-") (pintype "bidirectional"))
      (node (ref "U2") (pin "3X") (pinfunction "3X_3X") (pintype "bidirectional"))
    )
    (net (code "20") (name "/S8") (class "Default")
      (node (ref "R8") (pin "2") (pinfunction "2_2") (pintype "passive"))
      (node (ref "T8") (pin "-") (pinfunction "-_-") (pintype "bidirectional"))
      (node (ref "U2") (pin "0Y") (pinfunction "0Y_0Y") (pintype "bidirectional"))
    )
    (net (code "21") (name "/S9") (class "Default")
      (node (ref "R9") (pin "2") (pinfunction "2_2") (pintype "passive"))
      (node (ref "T9") (pin "-") (pinfunction "-_-") (pintype "bidirectional"))
      (node (ref "U2") (pin "2Y") (pinfunction "2Y_2Y") (pintype "bidirectional"))
    )
    (net (code "22") (name "/S10") (class "Default")
      (node (ref "R10") (pin "2") (pinfunction "2_2") (pintype "passive"))
      (node (ref "T10") (pin "-") (pinfunction "-_-") (pintype "bidirectional"))
      (node (ref "U2") (pin "3Y") (pinfunction "3Y_3Y") (pintype "bidirectional"))
    )
    (net (code "23") (name "/S11") (class "Default")
      (node (ref "R11") (pin "2") (pinfunction "2_2") (pintype "passive"))
      (node (ref "T11") (pin "-") (pinfunction "-_-") (pintype "bidirectional"))
      (node (ref "U2") (pin "1Y") (pinfunction "1Y_1Y") (pintype "bidirectional"))
    )
    (net (code "24") (name "/S12") (class "Default")
      (node (ref "R12") (pin "2") (pinfunction "2_2") (pintype "passive"))
      (node (ref "T12") (pin "-") (pinfunction "-_-") (pintype "bidirectional"))
      (node (ref "U3") (pin "3X") (pinfunction "3X_3X") (pintype "bidirectional"))
    )
    (net (code "25") (name "/S13") (class "Default")
      (node (ref "R13") (pin "2") (pinfunction "2_2") (pintype "passive"))
      (node (ref "T13") (pin "-") (pinfunction "-_-") (pintype "bidirectional"))
      (node (ref "U3") (pin "2X") (pinfunction "2X_2X") (pintype "bidirectional"))
    )
    (net (code "26") (name "/S14") (class "Default")
      (node (ref "R14") (pin "2") (pinfunction "2_2") (pintype "passive"))
      (node (ref "T14") (pin "-") (pinfunction "-_-") (pintype "bidirectional"))
      (node (ref "U3") (pin "0Y") (pinfunction "0Y_0Y") (pintype "bidirectional"))
    )
    (net (code "27") (name "/S15") (class "Default")
      (node (ref "R15") (pin "2") (pinfunction "2_2") (pintype "passive"))
      (node (ref "T15") (pin "-") (pinfunction "-_-") (pintype "bidirectional"))
      (node (ref "U3") (pin "2Y") (pinfunction "2Y_2Y") (pintype "bidirectional"))
    )
    (net (code "28") (name "/S16") (class "Default")
      (node (ref "R16") (pin "2") (pinfunction "2_2") (pintype "passive"))
      (node (ref "T16") (pin "-") (pinfunction "-_-") (pintype "bidirectional"))
      (node (ref "U3") (pin "1X") (pinfunction "1X_1X") (pintype "bidirectional"))
    )
    (net (code "29") (name "/S17") (class "Default")
      (node (ref "R17") (pin "2") (pinfunction "2_2") (pintype "passive"))
      (node (ref "T17") (pin "-") (pinfunction "-_-") (pintype "bidirectional"))
      (node (ref "U3") (pin "0X") (pinfunction "0X_0X") (pintype "bidirectional"))
    )
    (net (code "30") (name "/S18") (class "Default")
      (node (ref "R18") (pin "2") (pinfunction "2_2") (pintype "passive"))
      (node (ref "T18") (pin "-") (pinfunction "-_-") (pintype "bidirectional"))
      (node (ref "U3") (pin "3Y") (pinfunction "3Y_3Y") (pintype "bidirectional"))
    )
    (net (code "31") (name "/S19") (class "Default")
      (node (ref "R19") (pin "2") (pinfunction "2_2") (pintype "passive"))
      (node (ref "T19") (pin "-") (pinfunction "-_-") (pintype "bidirectional"))
      (node (ref "U3") (pin "1Y") (pinfunction "1Y_1Y") (pintype "bidirectional"))
    )
    (net (code "32") (name "/S20") (class "Default")
      (node (ref "R20") (pin "2") (pinfunction "2_2") (pintype "passive"))
      (node (ref "T20") (pin "-") (pinfunction "-_-") (pintype "bidirectional"))
      (node (ref "U1") (pin "3X") (pinfunction "3X_3X") (pintype "bidirectional"))
    )
    (net (code "33") (name "/S21") (class "Default")
      (node (ref "R21") (pin "2") (pinfunction "2_2") (pintype "passive"))
      (node (ref "T21") (pin "-") (pinfunction "-_-") (pintype "bidirectional"))
      (node (ref "U1") (pin "0X") (pinfunction "0X_0X") (pintype "bidirectional"))
    )
    (net (code "34") (name "/S22") (class "Default")
      (node (ref "R22") (pin "2") (pinfunction "2_2") (pintype "passive"))
      (node (ref "T22") (pin "-") (pinfunction "-_-") (pintype "bidirectional"))
      (node (ref "U1") (pin "1X") (pinfunction "1X_1X") (pintype "bidirectional"))
    )
    (net (code "35") (name "/S23") (class "Default")
      (node (ref "R23") (pin "2") (pinfunction "2_2") (pintype "passive"))
      (node (ref "T23") (pin "-") (pinfunction "-_-") (pintype "bidirectional"))
      (node (ref "U1") (pin "2X") (pinfunction "2X_2X") (pintype "bidirectional"))
    )
    (net (code "36") (name "/S24") (class "Default")
      (node (ref "R24") (pin "2") (pinfunction "2_2") (pintype "passive"))
      (node (ref "T24") (pin "-") (pinfunction "-_-") (pintype "bidirectional"))
      (node (ref "U1") (pin "0Y") (pinfunction "0Y_0Y") (pintype "bidirectional"))
    )
    (net (code "37") (name "/S25") (class "Default")
      (node (ref "R25") (pin "2") (pinfunction "2_2") (pintype "passive"))
      (node (ref "R26") (pin "2") (pinfunction "2_2") (pintype "passive"))
      (node (ref "R27") (pin "2") (pinfunction "2_2") (pintype "passive"))
      (node (ref "T25") (pin "-") (pinfunction "-_-") (pintype "bidirectional"))
      (node (ref "T26") (pin "-") (pinfunction "-_-") (pintype "bidirectional"))
      (node (ref "T27") (pin "-") (pinfunction "-_-") (pintype "bidirectional"))
      (node (ref "U4") (pin "10") (pinfunction "PC2/SPI2_MISO/OTG_HS_ULPI_DIR/FMC_SDNE0/EVENTOUT_10") (pintype "bidirectional"))
    )
    (net (code "38") (name "/S26") (class "Default")
      (node (ref "R28") (pin "2") (pinfunction "2_2") (pintype "passive"))
      (node (ref "R29") (pin "2") (pinfunction "2_2") (pintype "passive"))
      (node (ref "R30") (pin "2") (pinfunction "2_2") (pintype "passive"))
      (node (ref "T28") (pin "-") (pinfunction "-_-") (pintype "bidirectional"))
      (node (ref "T29") (pin "-") (pinfunction "-_-") (pintype "bidirectional"))
      (node (ref "T30") (pin "-") (pinfunction "-_-") (pintype "bidirectional"))
      (node (ref "U4") (pin "27") (pinfunction "PB1/TIM1_CH3N/TIM3_CH4/TIM8_CH3N/OTG_HS_ULPI_D2/SDIO_D2/EVENTOUT_27") (pintype "bidirectional"))
    )
    (net (code "39") (name "/S27") (class "Default")
      (node (ref "R61") (pin "2") (pinfunction "2_2") (pintype "passive"))
      (node (ref "T31") (pin "-") (pinfunction "-_-") (pintype "bidirectional"))
      (node (ref "U4") (pin "11") (pinfunction "PC3/SPI2_MOSI/I2S2_SD/OTG_HS_ULPI_NXT/FMC_SDCKE0/EVENTOUT_11") (pintype "bidirectional"))
    )
    (net (code "40") (name "/S28") (class "Default")
      (node (ref "R62") (pin "2") (pinfunction "2_2") (pintype "passive"))
      (node (ref "T32") (pin "-") (pinfunction "-_-") (pintype "bidirectional"))
      (node (ref "U4") (pin "23") (pinfunction "PA7/TIM1_CH1N/TIM3_CH2/TIM8_CH1N/SPI1_MOSI/I2S1_SD/TIM14_CH1/FMC_SDNWE/EVENTOUT_23") (pintype "bidirectional"))
    )
    (net (code "41") (name "/S29") (class "Default")
      (node (ref "R63") (pin "2") (pinfunction "2_2") (pintype "passive"))
      (node (ref "T33") (pin "-") (pinfunction "-_-") (pintype "bidirectional"))
      (node (ref "U4") (pin "24") (pinfunction "PC4/I2S1_MCK/SPDIFRX_IN2/FMC_SDNE0/EVENTOUT_24") (pintype "bidirectional"))
    )
    (net (code "42") (name "/S30") (class "Default")
      (node (ref "R64") (pin "2") (pinfunction "2_2") (pintype "passive"))
      (node (ref "T34") (pin "-") (pinfunction "-_-") (pintype "bidirectional"))
      (node (ref "U4") (pin "22") (pinfunction "PA6/TIM1_BKIN/TIM3_CH1/TIM8_BKIN/SPI1_MISO/I2S2_MCK/TIM13_CH1/DCMI_PIXCLK/EVENTOUT_22") (pintype "bidirectional"))
    )
    (net (code "43") (name "/U1A") (class "Default")
      (node (ref "U1") (pin "A") (pinfunction "A_A") (pintype "bidirectional"))
      (node (ref "U4") (pin "59") (pinfunction "PB7/TIM4_CH2/I2C1_SDA/USART1_RX/SPDIFRX_IN0/FMC_NL/DCMI_VSYNC/EVENTOUT_59") (pintype "bidirectional"))
    )
    (net (code "44") (name "/U1B") (class "Default")
      (node (ref "U1") (pin "B") (pinfunction "B_B") (pintype "bidirectional"))
      (node (ref "U4") (pin "62") (pinfunction "PB9/TIM2_CH2/TIM4_CH4/TIM11_CH1/I2C1_SDA/SPI2_NSS/I2S2_WS/SAI1_FS_B/CAN1_TX/SDIO_D5/DCMI_D7/EVENTOUT_62") (pintype "bidirectional"))
    )
    (net (code "45") (name "/U1X") (class "Default")
      (node (ref "U1") (pin "X-COM") (pinfunction "X-COM_X-COM") (pintype "bidirectional"))
      (node (ref "U4") (pin "8") (pinfunction "PC0/SAI1_MCLK_B/OTG_HS_ULPI_STP/FMC_SDNWE/EVENTOUT_8") (pintype "bidirectional"))
    )
    (net (code "46") (name "/U1Y") (class "Default")
      (node (ref "U1") (pin "Y-COM") (pinfunction "Y-COM_Y-COM") (pintype "bidirectional"))
      (node (ref "U4") (pin "9") (pinfunction "PC1/SPI3_MOSI/I2S3_SD/SAI1_SD_A/SPI2_MOSI/I2S2_SD/EVENTOUT_9") (pintype "bidirectional"))
    )
    (net (code "47") (name "/U2A") (class "Default")
      (node (ref "U2") (pin "A") (pinfunction "A_A") (pintype "bidirectional"))
      (node (ref "U4") (pin "20") (pinfunction "PA4/SPI1_NSS/I2S1_WS/SPI3_NSS/I2S3_WS/USART2_CK/OTG_HS_SOF/DCMI_HSYNC/EVENTOUT_20") (pintype "bidirectional"))
    )
    (net (code "48") (name "/U2B") (class "Default")
      (node (ref "U2") (pin "B") (pinfunction "B_B") (pintype "bidirectional"))
      (node (ref "U4") (pin "21") (pinfunction "PA5/TIM2_CH1/TIM2_ETR/TIM8_CH1N/SPI1_SCK/I2S1_CK/OTG_HS_ULPI_CK/EVENTOUT_21") (pintype "bidirectional"))
    )
    (net (code "49") (name "/U2X") (class "Default")
      (node (ref "U2") (pin "X-COM") (pinfunction "X-COM_X-COM") (pintype "bidirectional"))
      (node (ref "U4") (pin "16") (pinfunction "PA2/TIM2_CH3/TIM5_CH3/TIM9_CH1/USART2_TX/SAI2_SCK_B/EVENTOUT_16") (pintype "bidirectional"))
    )
    (net (code "50") (name "/U2Y") (class "Default")
      (node (ref "U2") (pin "Y-COM") (pinfunction "Y-COM_Y-COM") (pintype "bidirectional"))
      (node (ref "U4") (pin "17") (pinfunction "PA3/TIM2_CH4/TIM5_CH4/TIM9_CH2/SAI1_FS_A/USART2_RX/OTG_HS_ULPI_D0/EVENTOUT_17") (pintype "bidirectional"))
    )
    (net (code "51") (name "/U3A") (class "Default")
      (node (ref "U3") (pin "A") (pinfunction "A_A") (pintype "bidirectional"))
      (node (ref "U4") (pin "33") (pinfunction "PB12/TIM1_BKIN/I2C2_SMBA/SPI2_NSS/I2S2_WS/SAI1_SCK_B/USART3_CK/CAN2_RX/OTG_HS_ULPI_D5/OTG_HS_ID/EVENTOUT_33") (pintype "bidirectional"))
    )
    (net (code "52") (name "/U3B") (class "Default")
      (node (ref "U3") (pin "B") (pinfunction "B_B") (pintype "bidirectional"))
      (node (ref "U4") (pin "34") (pinfunction "PB13/TIM1_CH1N/SPI2_SCK/I2S2_CK/USART3_CTS/CAN2_TX/OTG_HS_ULPI_D6/EVENTOUT_34") (pintype "bidirectional"))
    )
    (net (code "53") (name "/U3X") (class "Default")
      (node (ref "U3") (pin "X-COM") (pinfunction "X-COM_X-COM") (pintype "bidirectional"))
      (node (ref "U4") (pin "25") (pinfunction "PC5/USART3_RX/SPDIFRX_IN3/FMC_SDCKE0/EVENTOUT_25") (pintype "bidirectional"))
    )
    (net (code "54") (name "/U3Y") (class "Default")
      (node (ref "U3") (pin "Y-COM") (pinfunction "Y-COM_Y-COM") (pintype "bidirectional"))
      (node (ref "U4") (pin "26") (pinfunction "PB0/TIM1_CH2N/TIM3_CH3/TIM8_CH2N/SPI3_MOSI/I2S3_SD/UART4_CTS/OTG_HS_ULPI_D1/SDIO_D1/EVENTOUT_26") (pintype "bidirectional"))
    )
    (net (code "55") (name "GND") (class "Default")
      (node (ref "C1") (pin "2") (pinfunction "2_2") (pintype "passive"))
      (node (ref "C11") (pin "2") (pinfunction "2_2") (pintype "passive"))
      (node (ref "C12") (pin "2") (pinfunction "2_2") (pintype "passive"))
      (node (ref "C13") (pin "2") (pinfunction "2_2") (pintype "passive"))
      (node (ref "C14") (pin "2") (pinfunction "2_2") (pintype "passive"))
      (node (ref "C2") (pin "2") (pinfunction "2_2") (pintype "passive"))
      (node (ref "C3") (pin "2") (pinfunction "2_2") (pintype "passive"))
      (node (ref "C4") (pin "2") (pinfunction "2_2") (pintype "passive"))
      (node (ref "C5") (pin "2") (pinfunction "2_2") (pintype "passive"))
      (node (ref "C6") (pin "2") (pinfunction "2_2") (pintype "passive"))
      (node (ref "C7") (pin "2") (pinfunction "2_2") (pintype "passive"))
      (node (ref "C8") (pin "2") (pinfunction "2_2") (pintype "passive"))
      (node (ref "C9") (pin "1") (pinfunction "1_1") (pintype "passive"))
      (node (ref "L1") (pin "C") (pinfunction "C_C") (pintype "passive"))
      (node (ref "L10") (pin "C") (pinfunction "C_C") (pintype "passive"))
      (node (ref "L11") (pin "C") (pinfunction "C_C") (pintype "passive"))
      (node (ref "L12") (pin "C") (pinfunction "C_C") (pintype "passive"))
      (node (ref "L13") (pin "C") (pinfunction "C_C") (pintype "passive"))
      (node (ref "L14") (pin "C") (pinfunction "C_C") (pintype "passive"))
      (node (ref "L15") (pin "C") (pinfunction "C_C") (pintype "passive"))
      (node (ref "L16") (pin "C") (pinfunction "C_C") (pintype "passive"))
      (node (ref "L17") (pin "C") (pinfunction "C_C") (pintype "passive"))
      (node (ref "L18") (pin "C") (pinfunction "C_C") (pintype "passive"))
      (node (ref "L19") (pin "C") (pinfunction "C_C") (pintype "passive"))
      (node (ref "L2") (pin "C") (pinfunction "C_C") (pintype "passive"))
      (node (ref "L20") (pin "C") (pinfunction "C_C") (pintype "passive"))
      (node (ref "L21") (pin "C") (pinfunction "C_C") (pintype "passive"))
      (node (ref "L22") (pin "C") (pinfunction "C_C") (pintype "passive"))
      (node (ref "L23") (pin "C") (pinfunction "C_C") (pintype "passive"))
      (node (ref "L24") (pin "C") (pinfunction "C_C") (pintype "passive"))
      (node (ref "L25") (pin "C") (pinfunction "C_C") (pintype "passive"))
      (node (ref "L26") (pin "C") (pinfunction "C_C") (pintype "passive"))
      (node (ref "L27") (pin "C") (pinfunction "C_C") (pintype "passive"))
      (node (ref "L28") (pin "C") (pinfunction "C_C") (pintype "passive"))
      (node (ref "L29") (pin "C") (pinfunction "C_C") (pintype "passive"))
      (node (ref "L3") (pin "C") (pinfunction "C_C") (pintype "passive"))
      (node (ref "L30") (pin "C") (pinfunction "C_C") (pintype "passive"))
      (node (ref "L31") (pin "C") (pinfunction "C_C") (pintype "passive"))
      (node (ref "L32") (pin "C") (pinfunction "C_C") (pintype "passive"))
      (node (ref "L33") (pin "C") (pinfunction "C_C") (pintype "passive"))
      (node (ref "L34") (pin "C") (pinfunction "C_C") (pintype "passive"))
      (node (ref "L35") (pin "C") (pinfunction "C_C") (pintype "passive"))
      (node (ref "L36") (pin "C") (pinfunction "C_C") (pintype "passive"))
      (node (ref "L37") (pin "C") (pinfunction "C_C") (pintype "passive"))
      (node (ref "L4") (pin "C") (pinfunction "C_C") (pintype "passive"))
      (node (ref "L5") (pin "C") (pinfunction "C_C") (pintype "passive"))
      (node (ref "L6") (pin "C") (pinfunction "C_C") (pintype "passive"))
      (node (ref "L7") (pin "C") (pinfunction "C_C") (pintype "passive"))
      (node (ref "L8") (pin "C") (pinfunction "C_C") (pintype "passive"))
      (node (ref "L9") (pin "C") (pinfunction "C_C") (pintype "passive"))
      (node (ref "R1") (pin "1") (pinfunction "1_1") (pintype "passive"))
      (node (ref "R10") (pin "1") (pinfunction "1_1") (pintype "passive"))
      (node (ref "R11") (pin "1") (pinfunction "1_1") (pintype "passive"))
      (node (ref "R12") (pin "1") (pinfunction "1_1") (pintype "passive"))
      (node (ref "R13") (pin "1") (pinfunction "1_1") (pintype "passive"))
      (node (ref "R14") (pin "1") (pinfunction "1_1") (pintype "passive"))
      (node (ref "R15") (pin "1") (pinfunction "1_1") (pintype "passive"))
      (node (ref "R16") (pin "1") (pinfunction "1_1") (pintype "passive"))
      (node (ref "R17") (pin "1") (pinfunction "1_1") (pintype "passive"))
      (node (ref "R18") (pin "1") (pinfunction "1_1") (pintype "passive"))
      (node (ref "R19") (pin "1") (pinfunction "1_1") (pintype "passive"))
      (node (ref "R2") (pin "1") (pinfunction "1_1") (pintype "passive"))
      (node (ref "R20") (pin "1") (pinfunction "1_1") (pintype "passive"))
      (node (ref "R21") (pin "1") (pinfunction "1_1") (pintype "passive"))
      (node (ref "R22") (pin "1") (pinfunction "1_1") (pintype "passive"))
      (node (ref "R23") (pin "1") (pinfunction "1_1") (pintype "passive"))
      (node (ref "R24") (pin "1") (pinfunction "1_1") (pintype "passive"))
      (node (ref "R25") (pin "1") (pinfunction "1_1") (pintype "passive"))
      (node (ref "R26") (pin "1") (pinfunction "1_1") (pintype "passive"))
      (node (ref "R27") (pin "1") (pinfunction "1_1") (pintype "passive"))
      (node (ref "R28") (pin "1") (pinfunction "1_1") (pintype "passive"))
      (node (ref "R29") (pin "1") (pinfunction "1_1") (pintype "passive"))
      (node (ref "R3") (pin "1") (pinfunction "1_1") (pintype "passive"))
      (node (ref "R30") (pin "1") (pinfunction "1_1") (pintype "passive"))
      (node (ref "R4") (pin "1") (pinfunction "1_1") (pintype "passive"))
      (node (ref "R5") (pin "1") (pinfunction "1_1") (pintype "passive"))
      (node (ref "R6") (pin "1") (pinfunction "1_1") (pintype "passive"))
      (node (ref "R61") (pin "1") (pinfunction "1_1") (pintype "passive"))
      (node (ref "R62") (pin "1") (pinfunction "1_1") (pintype "passive"))
      (node (ref "R63") (pin "1") (pinfunction "1_1") (pintype "passive"))
      (node (ref "R64") (pin "1") (pinfunction "1_1") (pintype "passive"))
      (node (ref "R7") (pin "1") (pinfunction "1_1") (pintype "passive"))
      (node (ref "R78") (pin "1") (pinfunction "1_1") (pintype "passive"))
      (node (ref "R8") (pin "1") (pinfunction "1_1") (pintype "passive"))
      (node (ref "R9") (pin "1") (pinfunction "1_1") (pintype "passive"))
      (node (ref "U1") (pin "INH") (pinfunction "INH_INH") (pintype "bidirectional"))
      (node (ref "U1") (pin "VEE") (pinfunction "VEE_VEE") (pintype "bidirectional"))
      (node (ref "U1") (pin "VSS") (pinfunction "VSS_VSS") (pintype "bidirectional"))
      (node (ref "U2") (pin "INH") (pinfunction "INH_INH") (pintype "bidirectional"))
      (node (ref "U2") (pin "VEE") (pinfunction "VEE_VEE") (pintype "bidirectional"))
      (node (ref "U2") (pin "VSS") (pinfunction "VSS_VSS") (pintype "bidirectional"))
      (node (ref "U3") (pin "INH") (pinfunction "INH_INH") (pintype "bidirectional"))
      (node (ref "U3") (pin "VEE") (pinfunction "VEE_VEE") (pintype "bidirectional"))
      (node (ref "U3") (pin "VSS") (pinfunction "VSS_VSS") (pintype "bidirectional"))
      (node (ref "U4") (pin "12") (pinfunction "VSSA/VREF-_12") (pintype "power_in"))
      (node (ref "U4") (pin "18") (pinfunction "VSS_18") (pintype "power_in"))
      (node (ref "U4") (pin "31") (pinfunction "VSS_31") (pintype "power_in"))
      (node (ref "U4") (pin "47") (pinfunction "VSS_47") (pintype "power_in"))
      (node (ref "U4") (pin "63") (pinfunction "VSS_63") (pintype "power_in"))
      (node (ref "XH2") (pin "P$2") (pinfunction "2_P$2") (pintype "bidirectional"))
    )
    (net (code "56") (name "Net-(L1-PadA)") (class "Default")
      (node (ref "L1") (pin "A") (pinfunction "A_A") (pintype "passive"))
      (node (ref "R31") (pin "1") (pinfunction "1_1") (pintype "passive"))
    )
    (net (code "57") (name "Net-(L2-PadA)") (class "Default")
      (node (ref "L2") (pin "A") (pinfunction "A_A") (pintype "passive"))
      (node (ref "R32") (pin "1") (pinfunction "1_1") (pintype "passive"))
    )
    (net (code "58") (name "Net-(L3-PadA)") (class "Default")
      (node (ref "L3") (pin "A") (pinfunction "A_A") (pintype "passive"))
      (node (ref "R33") (pin "1") (pinfunction "1_1") (pintype "passive"))
    )
    (net (code "59") (name "Net-(L4-PadA)") (class "Default")
      (node (ref "L4") (pin "A") (pinfunction "A_A") (pintype "passive"))
      (node (ref "R34") (pin "1") (pinfunction "1_1") (pintype "passive"))
    )
    (net (code "60") (name "Net-(L5-PadA)") (class "Default")
      (node (ref "L5") (pin "A") (pinfunction "A_A") (pintype "passive"))
      (node (ref "R35") (pin "1") (pinfunction "1_1") (pintype "passive"))
    )
    (net (code "61") (name "Net-(L6-PadA)") (class "Default")
      (node (ref "L6") (pin "A") (pinfunction "A_A") (pintype "passive"))
      (node (ref "R36") (pin "1") (pinfunction "1_1") (pintype "passive"))
    )
    (net (code "62") (name "Net-(L7-PadA)") (class "Default")
      (node (ref "L7") (pin "A") (pinfunction "A_A") (pintype "passive"))
      (node (ref "R37") (pin "1") (pinfunction "1_1") (pintype "passive"))
    )
    (net (code "63") (name "Net-(L8-PadA)") (class "Default")
      (node (ref "L8") (pin "A") (pinfunction "A_A") (pintype "passive"))
      (node (ref "R38") (pin "1") (pinfunction "1_1") (pintype "passive"))
    )
    (net (code "64") (name "Net-(L9-PadA)") (class "Default")
      (node (ref "L9") (pin "A") (pinfunction "A_A") (pintype "passive"))
      (node (ref "R39") (pin "1") (pinfunction "1_1") (pintype "passive"))
    )
    (net (code "65") (name "Net-(L10-PadA)") (class "Default")
      (node (ref "L10") (pin "A") (pinfunction "A_A") (pintype "passive"))
      (node (ref "R40") (pin "1") (pinfunction "1_1") (pintype "passive"))
    )
    (net (code "66") (name "Net-(L11-PadA)") (class "Default")
      (node (ref "L11") (pin "A") (pinfunction "A_A") (pintype "passive"))
      (node (ref "R41") (pin "1") (pinfunction "1_1") (pintype "passive"))
    )
    (net (code "67") (name "Net-(L12-PadA)") (class "Default")
      (node (ref "L12") (pin "A") (pinfunction "A_A") (pintype "passive"))
      (node (ref "R42") (pin "1") (pinfunction "1_1") (pintype "passive"))
    )
    (net (code "68") (name "Net-(L13-PadA)") (class "Default")
      (node (ref "L13") (pin "A") (pinfunction "A_A") (pintype "passive"))
      (node (ref "R43") (pin "1") (pinfunction "1_1") (pintype "passive"))
    )
    (net (code "69") (name "Net-(L14-PadA)") (class "Default")
      (node (ref "L14") (pin "A") (pinfunction "A_A") (pintype "passive"))
      (node (ref "R44") (pin "1") (pinfunction "1_1") (pintype "passive"))
    )
    (net (code "70") (name "Net-(L15-PadA)") (class "Default")
      (node (ref "L15") (pin "A") (pinfunction "A_A") (pintype "passive"))
      (node (ref "R45") (pin "1") (pinfunction "1_1") (pintype "passive"))
    )
    (net (code "71") (name "Net-(L16-PadA)") (class "Default")
      (node (ref "L16") (pin "A") (pinfunction "A_A") (pintype "passive"))
      (node (ref "R46") (pin "1") (pinfunction "1_1") (pintype "passive"))
    )
    (net (code "72") (name "Net-(L17-PadA)") (class "Default")
      (node (ref "L17") (pin "A") (pinfunction "A_A") (pintype "passive"))
      (node (ref "R47") (pin "1") (pinfunction "1_1") (pintype "passive"))
    )
    (net (code "73") (name "Net-(L18-PadA)") (class "Default")
      (node (ref "L18") (pin "A") (pinfunction "A_A") (pintype "passive"))
      (node (ref "R48") (pin "1") (pinfunction "1_1") (pintype "passive"))
    )
    (net (code "74") (name "Net-(L19-PadA)") (class "Default")
      (node (ref "L19") (pin "A") (pinfunction "A_A") (pintype "passive"))
      (node (ref "R49") (pin "1") (pinfunction "1_1") (pintype "passive"))
    )
    (net (code "75") (name "Net-(L20-PadA)") (class "Default")
      (node (ref "L20") (pin "A") (pinfunction "A_A") (pintype "passive"))
      (node (ref "R50") (pin "1") (pinfunction "1_1") (pintype "passive"))
    )
    (net (code "76") (name "Net-(L21-PadA)") (class "Default")
      (node (ref "L21") (pin "A") (pinfunction "A_A") (pintype "passive"))
      (node (ref "R51") (pin "1") (pinfunction "1_1") (pintype "passive"))
    )
    (net (code "77") (name "Net-(L22-PadA)") (class "Default")
      (node (ref "L22") (pin "A") (pinfunction "A_A") (pintype "passive"))
      (node (ref "R52") (pin "1") (pinfunction "1_1") (pintype "passive"))
    )
    (net (code "78") (name "Net-(L23-PadA)") (class "Default")
      (node (ref "L23") (pin "A") (pinfunction "A_A") (pintype "passive"))
      (node (ref "R53") (pin "1") (pinfunction "1_1") (pintype "passive"))
    )
    (net (code "79") (name "Net-(L24-PadA)") (class "Default")
      (node (ref "L24") (pin "A") (pinfunction "A_A") (pintype "passive"))
      (node (ref "R54") (pin "1") (pinfunction "1_1") (pintype "passive"))
    )
    (net (code "80") (name "Net-(L25-PadA)") (class "Default")
      (node (ref "L25") (pin "A") (pinfunction "A_A") (pintype "passive"))
      (node (ref "R55") (pin "1") (pinfunction "1_1") (pintype "passive"))
    )
    (net (code "81") (name "Net-(L26-PadA)") (class "Default")
      (node (ref "L26") (pin "A") (pinfunction "A_A") (pintype "passive"))
      (node (ref "R56") (pin "1") (pinfunction "1_1") (pintype "passive"))
    )
    (net (code "82") (name "Net-(L27-PadA)") (class "Default")
      (node (ref "L27") (pin "A") (pinfunction "A_A") (pintype "passive"))
      (node (ref "R57") (pin "1") (pinfunction "1_1") (pintype "passive"))
    )
    (net (code "83") (name "Net-(L28-PadA)") (class "Default")
      (node (ref "L28") (pin "A") (pinfunction "A_A") (pintype "passive"))
      (node (ref "R58") (pin "1") (pinfunction "1_1") (pintype "passive"))
    )
    (net (code "84") (name "Net-(L29-PadA)") (class "Default")
      (node (ref "L29") (pin "A") (pinfunction "A_A") (pintype "passive"))
      (node (ref "R59") (pin "1") (pinfunction "1_1") (pintype "passive"))
    )
    (net (code "85") (name "Net-(L30-PadA)") (class "Default")
      (node (ref "L30") (pin "A") (pinfunction "A_A") (pintype "passive"))
      (node (ref "R60") (pin "1") (pinfunction "1_1") (pintype "passive"))
    )
    (net (code "86") (name "Net-(L31-PadA)") (class "Default")
      (node (ref "L31") (pin "A") (pinfunction "A_A") (pintype "passive"))
      (node (ref "R65") (pin "1") (pinfunction "1_1") (pintype "passive"))
    )
    (net (code "87") (name "Net-(L32-PadA)") (class "Default")
      (node (ref "L32") (pin "A") (pinfunction "A_A") (pintype "passive"))
      (node (ref "R66") (pin "1") (pinfunction "1_1") (pintype "passive"))
    )
    (net (code "88") (name "Net-(L33-PadA)") (class "Default")
      (node (ref "L33") (pin "A") (pinfunction "A_A") (pintype "passive"))
      (node (ref "R67") (pin "1") (pinfunction "1_1") (pintype "passive"))
    )
    (net (code "89") (name "Net-(L34-PadA)") (class "Default")
      (node (ref "L34") (pin "A") (pinfunction "A_A") (pintype "passive"))
      (node (ref "R68") (pin "1") (pinfunction "1_1") (pintype "passive"))
    )
    (net (code "90") (name "Net-(L35-PadA)") (class "Default")
      (node (ref "L35") (pin "A") (pinfunction "A_A") (pintype "passive"))
      (node (ref "R69") (pin "1") (pinfunction "1_1") (pintype "passive"))
    )
    (net (code "91") (name "Net-(L36-PadA)") (class "Default")
      (node (ref "L36") (pin "A") (pinfunction "A_A") (pintype "passive"))
      (node (ref "R70") (pin "1") (pinfunction "1_1") (pintype "passive"))
    )
    (net (code "92") (name "Net-(L37-PadA)") (class "Default")
      (node (ref "L37") (pin "A") (pinfunction "A_A") (pintype "passive"))
      (node (ref "R71") (pin "1") (pinfunction "1_1") (pintype "passive"))
    )
    (net (code "93") (name "Net-(Q1-G1)") (class "Default")
      (node (ref "Q1") (pin "G") (pinfunction "G1_G") (pintype "bidirectional"))
      (node (ref "R72") (pin "2") (pinfunction "2_2") (pintype "passive"))
      (node (ref "R73") (pin "1") (pinfunction "1_1") (pintype "passive"))
    )
    (net (code "94") (name "Net-(U4-BOOT0)") (class "Default")
      (node (ref "R78") (pin "2") (pinfunction "2_2") (pintype "passive"))
      (node (ref "U4") (pin "60") (pinfunction "BOOT0_60") (pintype "input"))
    )
    (net (code "95") (name "Net-(U4-PH0-OSC_IN{slash}EVENTOUT)") (class "Default")
      (node (ref "C2") (pin "1") (pinfunction "1_1") (pintype "passive"))
      (node (ref "U4") (pin "5") (pinfunction "PH0-OSC_IN/EVENTOUT_5") (pintype "bidirectional"))
      (node (ref "X2") (pin "P$2") (pinfunction "2_P$2") (pintype "passive"))
    )
    (net (code "96") (name "Net-(U4-PH1-OSC_OUT{slash}EVENTOUT)") (class "Default")
      (node (ref "C3") (pin "1") (pinfunction "1_1") (pintype "passive"))
      (node (ref "U4") (pin "6") (pinfunction "PH1-OSC_OUT/EVENTOUT_6") (pintype "bidirectional"))
      (node (ref "X2") (pin "P$1") (pinfunction "1_P$1") (pintype "passive"))
    )
    (net (code "97") (name "Net-(U4-VCAP_1)") (class "Default")
      (node (ref "C1") (pin "1") (pinfunction "1_1") (pintype "passive"))
      (node (ref "U4") (pin "30") (pinfunction "VCAP_1_30") (pintype "power_in"))
    )
    (net (code "98") (name "unconnected-(U4-PA1{slash}TIM2_CH2{slash}TIM5_CH2{slash}USART2_RTS{slash}UART4_RX{slash}QUADSPI_BK1_IO3{slash}SAI2_MCLK_B{slash}EVENTOUT-Pad15)") (class "Default")
      (node (ref "U4") (pin "15") (pinfunction "PA1/TIM2_CH2/TIM5_CH2/USART2_RTS/UART4_RX/QUADSPI_BK1_IO3/SAI2_MCLK_B/EVENTOUT_15") (pintype "bidirectional"))
    )
    (net (code "99") (name "unconnected-(U4-PA8{slash}MCO1{slash}TIM1_CH1{slash}I2C3_SCL{slash}USART1_CK{slash}OTG_FS_SOF{slash}EVENTOUT-Pad41)") (class "Default")
      (node (ref "U4") (pin "41") (pinfunction "PA8/MCO1/TIM1_CH1/I2C3_SCL/USART1_CK/OTG_FS_SOF/EVENTOUT_41") (pintype "bidirectional"))
    )
    (net (code "100") (name "unconnected-(U4-PA9{slash}TIM1_CH2{slash}I2C3_SMBA{slash}SPI2_SCK{slash}I2S2_CK{slash}SAI1_SD_B{slash}USART1_TX{slash}DCMI_D0{slash}EVENTOUT-Pad42)") (class "Default")
      (node (ref "U4") (pin "42") (pinfunction "PA9/TIM1_CH2/I2C3_SMBA/SPI2_SCK/I2S2_CK/SAI1_SD_B/USART1_TX/DCMI_D0/EVENTOUT_42") (pintype "bidirectional"))
    )
    (net (code "101") (name "unconnected-(U4-PA10{slash}TIM1_CH3{slash}USART1_RX{slash}OTG_FS_ID{slash}DCMI_D1{slash}EVENTOUT-Pad43)") (class "Default")
      (node (ref "U4") (pin "43") (pinfunction "PA10/TIM1_CH3/USART1_RX/OTG_FS_ID/DCMI_D1/EVENTOUT_43") (pintype "bidirectional"))
    )
    (net (code "102") (name "unconnected-(U4-PA11{slash}TIM1_CH4{slash}USART1_CTS{slash}CAN1_RX{slash}OTG_FS_DM{slash}EVENTOUT-Pad44)") (class "Default")
      (node (ref "U4") (pin "44") (pinfunction "PA11/TIM1_CH4/USART1_CTS/CAN1_RX/OTG_FS_DM/EVENTOUT_44") (pintype "bidirectional"))
    )
    (net (code "103") (name "unconnected-(U4-PA12{slash}TIM1_ETR{slash}USART1_RTS{slash}SAI2_FS_B{slash}CAN1_TX{slash}OTG_FS_DP{slash}EVENTOUT-Pad45)") (class "Default")
      (node (ref "U4") (pin "45") (pinfunction "PA12/TIM1_ETR/USART1_RTS/SAI2_FS_B/CAN1_TX/OTG_FS_DP/EVENTOUT_45") (pintype "bidirectional"))
    )
    (net (code "104") (name "unconnected-(U4-PA15{slash}JTDI{slash}TIM2_CH1{slash}TIM2_ETR{slash}HDMI_CEC{slash}SPI1_NSS{slash}I2S1_WS{slash}SPI3_NSS{slash}I2S3_WS{slash}UART4_RTS{slash}EVENTOUT-Pad50)") (class "Default")
      (node (ref "U4") (pin "50") (pinfunction "PA15/JTDI/TIM2_CH1/TIM2_ETR/HDMI_CEC/SPI1_NSS/I2S1_WS/SPI3_NSS/I2S3_WS/UART4_RTS/EVENTOUT_50") (pintype "bidirectional"))
    )
    (net (code "105") (name "unconnected-(U4-PB2-BOOT1(PB2){slash}TIM2_CH4{slash}SAI1_SD_A{slash}SPI3_MOSI{slash}I2S3_SD{slash}QUADSPI_CLK{slash}OTG_HS_ULPI_D4{slash}SDIO_CK{slash}EVENTOUT-Pad28)") (class "Default")
      (node (ref "U4") (pin "28") (pinfunction "PB2-BOOT1(PB2)/TIM2_CH4/SAI1_SD_A/SPI3_MOSI/I2S3_SD/QUADSPI_CLK/OTG_HS_ULPI_D4/SDIO_CK/EVENTOUT_28") (pintype "bidirectional"))
    )
    (net (code "106") (name "unconnected-(U4-PB3(JTDO{slash}TRACESWO){slash}JTDO{slash}TRACESWO{slash}TIM2_CH2{slash}I2C2_SDA{slash}SPI1_SCK{slash}I2S1_CK{slash}SPI3_SCK{slash}I2S3_CK{slash}EVENTOUT-Pad55)") (class "Default")
      (node (ref "U4") (pin "55") (pinfunction "PB3(JTDO/TRACESWO)/JTDO/TRACESWO/TIM2_CH2/I2C2_SDA/SPI1_SCK/I2S1_CK/SPI3_SCK/I2S3_CK/EVENTOUT_55") (pintype "bidirectional"))
    )
    (net (code "107") (name "unconnected-(U4-PB4(NJTRST){slash}NJTRST{slash}TIM3_CH1{slash}I2C3_SDA{slash}SPI1_MISO{slash}SPI3_MISO{slash}SPI2_NSS{slash}I2S2_WS{slash}EVENTOUT-Pad56)") (class "Default")
      (node (ref "U4") (pin "56") (pinfunction "PB4(NJTRST)/NJTRST/TIM3_CH1/I2C3_SDA/SPI1_MISO/SPI3_MISO/SPI2_NSS/I2S2_WS/EVENTOUT_56") (pintype "bidirectional"))
    )
    (net (code "108") (name "unconnected-(U4-PB5{slash}TIM3_CH2{slash}I2C1_SMBA{slash}SPI1_MOSI{slash}I2S1_SD{slash}SPI3_MOSI{slash}I2S3_SD{slash}CAN2_RX{slash}OTG_HS_ULPI_D7{slash}FMC_SDCKE1{slash}DCMI_D10{slash}EVENTOUT-Pad57)") (class "Default")
      (node (ref "U4") (pin "57") (pinfunction "PB5/TIM3_CH2/I2C1_SMBA/SPI1_MOSI/I2S1_SD/SPI3_MOSI/I2S3_SD/CAN2_RX/OTG_HS_ULPI_D7/FMC_SDCKE1/DCMI_D10/EVENTOUT_57") (pintype "bidirectional"))
    )
    (net (code "109") (name "unconnected-(U4-PB6{slash}TIM4_CH1{slash}HDMI_CEC{slash}I2C1_SCL{slash}USART1_TX{slash}CAN2_TX{slash}QUADSPI_BK1_NCS{slash}FMC_SDNE1{slash}DCMI_D5{slash}EVENTOUT-Pad58)") (class "Default")
      (node (ref "U4") (pin "58") (pinfunction "PB6/TIM4_CH1/HDMI_CEC/I2C1_SCL/USART1_TX/CAN2_TX/QUADSPI_BK1_NCS/FMC_SDNE1/DCMI_D5/EVENTOUT_58") (pintype "bidirectional"))
    )
    (net (code "110") (name "unconnected-(U4-PB8{slash}TIM2_CH1{slash}TIM2_ETR{slash}TIM4_CH3{slash}TIM10_CH1{slash}I2C1_SCL{slash}CAN1_RX{slash}SDIO_D4{slash}DCMI_D6{slash}EVENTOUT-Pad61)") (class "Default")
      (node (ref "U4") (pin "61") (pinfunction "PB8/TIM2_CH1/TIM2_ETR/TIM4_CH3/TIM10_CH1/I2C1_SCL/CAN1_RX/SDIO_D4/DCMI_D6/EVENTOUT_61") (pintype "bidirectional"))
    )
    (net (code "111") (name "unconnected-(U4-PB10{slash}TIM2_CH3{slash}I2C2_SCL{slash}SPI2_SCK{slash}I2S2_CK{slash}SAI1_SCK_A{slash}USART3_TX{slash}OTG_HS_ULPI_D3{slash}EVENTOUT-Pad29)") (class "Default")
      (node (ref "U4") (pin "29") (pinfunction "PB10/TIM2_CH3/I2C2_SCL/SPI2_SCK/I2S2_CK/SAI1_SCK_A/USART3_TX/OTG_HS_ULPI_D3/EVENTOUT_29") (pintype "bidirectional"))
    )
    (net (code "112") (name "unconnected-(U4-PB14{slash}TIM1_CH2N{slash}TIM8_CH2N{slash}SPI2_MISO{slash}USART3_RTS{slash}TIM12_CH1{slash}OTG_HS_DM{slash}EVENTOUT-Pad35)") (class "Default")
      (node (ref "U4") (pin "35") (pinfunction "PB14/TIM1_CH2N/TIM8_CH2N/SPI2_MISO/USART3_RTS/TIM12_CH1/OTG_HS_DM/EVENTOUT_35") (pintype "bidirectional"))
    )
    (net (code "113") (name "unconnected-(U4-PB15{slash}RTC_REFIN{slash}TIM1_CH3N{slash}TIM8_CH3N{slash}SPI2_MOSI{slash}I2S2_SD{slash}TIM12_CH2{slash}OTG_HS_DP{slash}EVENTOUT-Pad36)") (class "Default")
      (node (ref "U4") (pin "36") (pinfunction "PB15/RTC_REFIN/TIM1_CH3N/TIM8_CH3N/SPI2_MOSI/I2S2_SD/TIM12_CH2/OTG_HS_DP/EVENTOUT_36") (pintype "bidirectional"))
    )
    (net (code "114") (name "unconnected-(U4-PC9{slash}MCO2{slash}TIM3_CH4{slash}TIM8_CH4{slash}I2C3_SDA{slash}I2S_CKIN{slash}UART5_CTS{slash}QUADSPI_BK1_IO0{slash}SDIO_D1{slash}DCMI_D3{slash}EVENTOUT-Pad40)") (class "Default")
      (node (ref "U4") (pin "40") (pinfunction "PC9/MCO2/TIM3_CH4/TIM8_CH4/I2C3_SDA/I2S_CKIN/UART5_CTS/QUADSPI_BK1_IO0/SDIO_D1/DCMI_D3/EVENTOUT_40") (pintype "bidirectional"))
    )
    (net (code "115") (name "unconnected-(U4-PC13{slash}EVENTOUT-Pad2)") (class "Default")
      (node (ref "U4") (pin "2") (pinfunction "PC13/EVENTOUT_2") (pintype "bidirectional"))
    )
    (net (code "116") (name "unconnected-(U4-PC14-OSC32_IN(PC14){slash}EVENTOUT-Pad3)") (class "Default")
      (node (ref "U4") (pin "3") (pinfunction "PC14-OSC32_IN(PC14)/EVENTOUT_3") (pintype "bidirectional"))
    )
    (net (code "117") (name "unconnected-(U4-PC15-OSC32_OUT(PC15){slash}EVENTOUT-Pad4)") (class "Default")
      (node (ref "U4") (pin "4") (pinfunction "PC15-OSC32_OUT(PC15)/EVENTOUT_4") (pintype "bidirectional"))
    )
    (net (code "118") (name "unconnected-(U4-PD2{slash}TIM3_ETR{slash}UART5_RX{slash}SDIO_CMD{slash}DCMI_D11{slash}EVENTOUT-Pad54)") (class "Default")
      (node (ref "U4") (pin "54") (pinfunction "PD2/TIM3_ETR/UART5_RX/SDIO_CMD/DCMI_D11/EVENTOUT_54") (pintype "bidirectional"))
    )
  )
)
